# 3dglove_p1.net
KiCad netlist of a schematic drawn in EAGLE
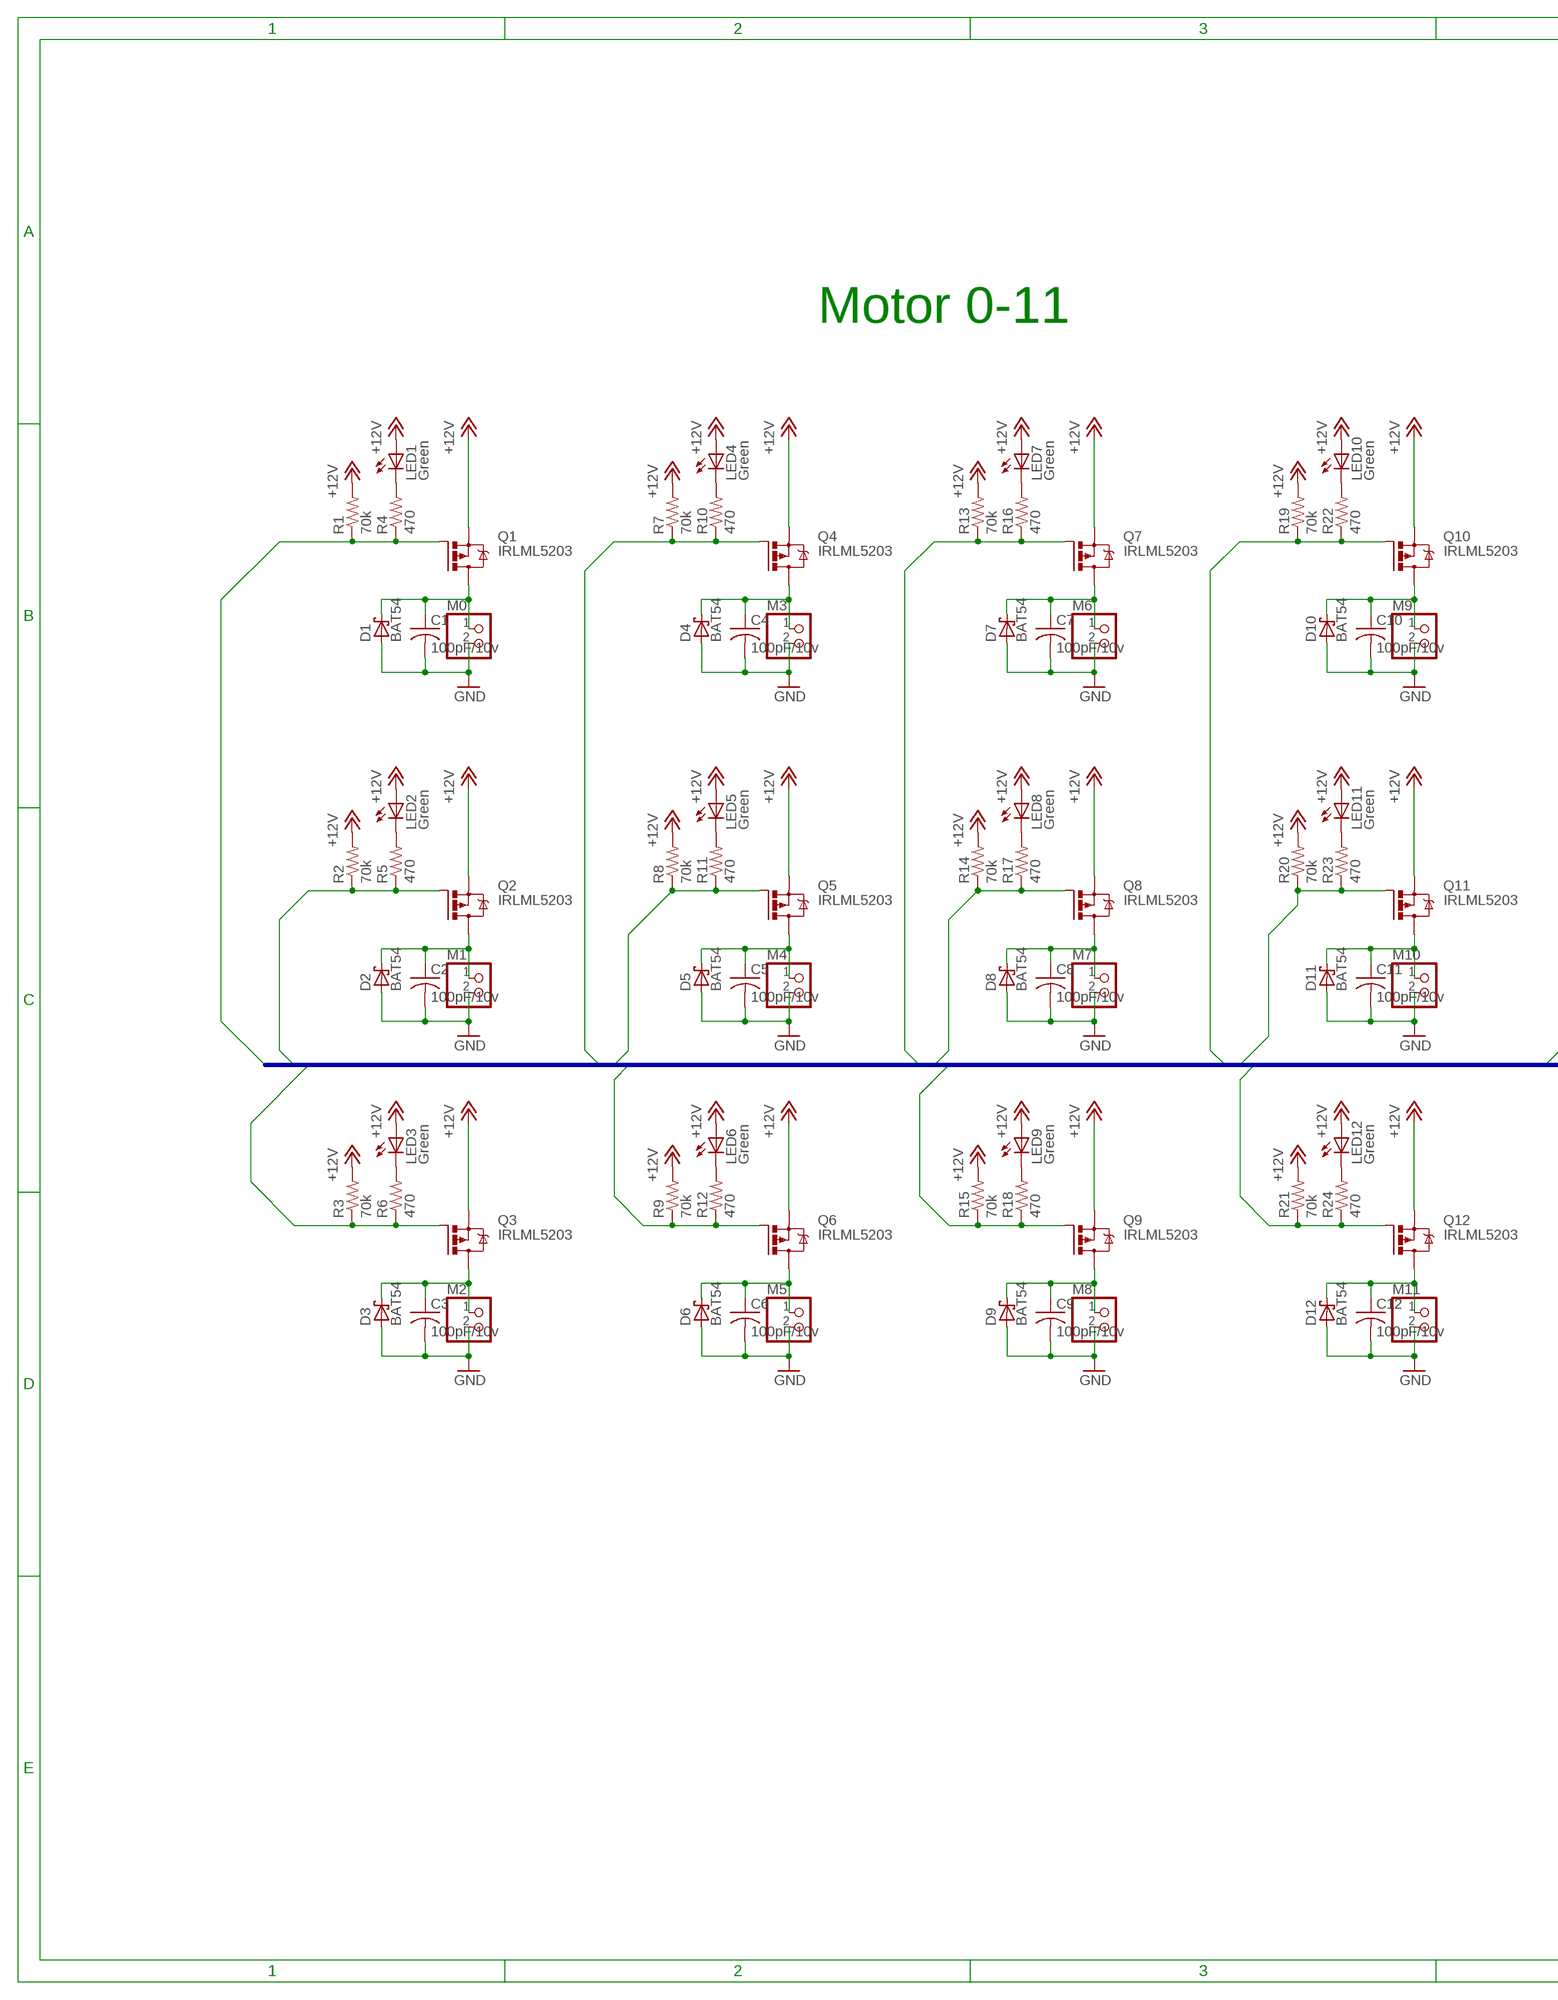
[diagram p0: schematic, sheet 1, part 1 of 2]
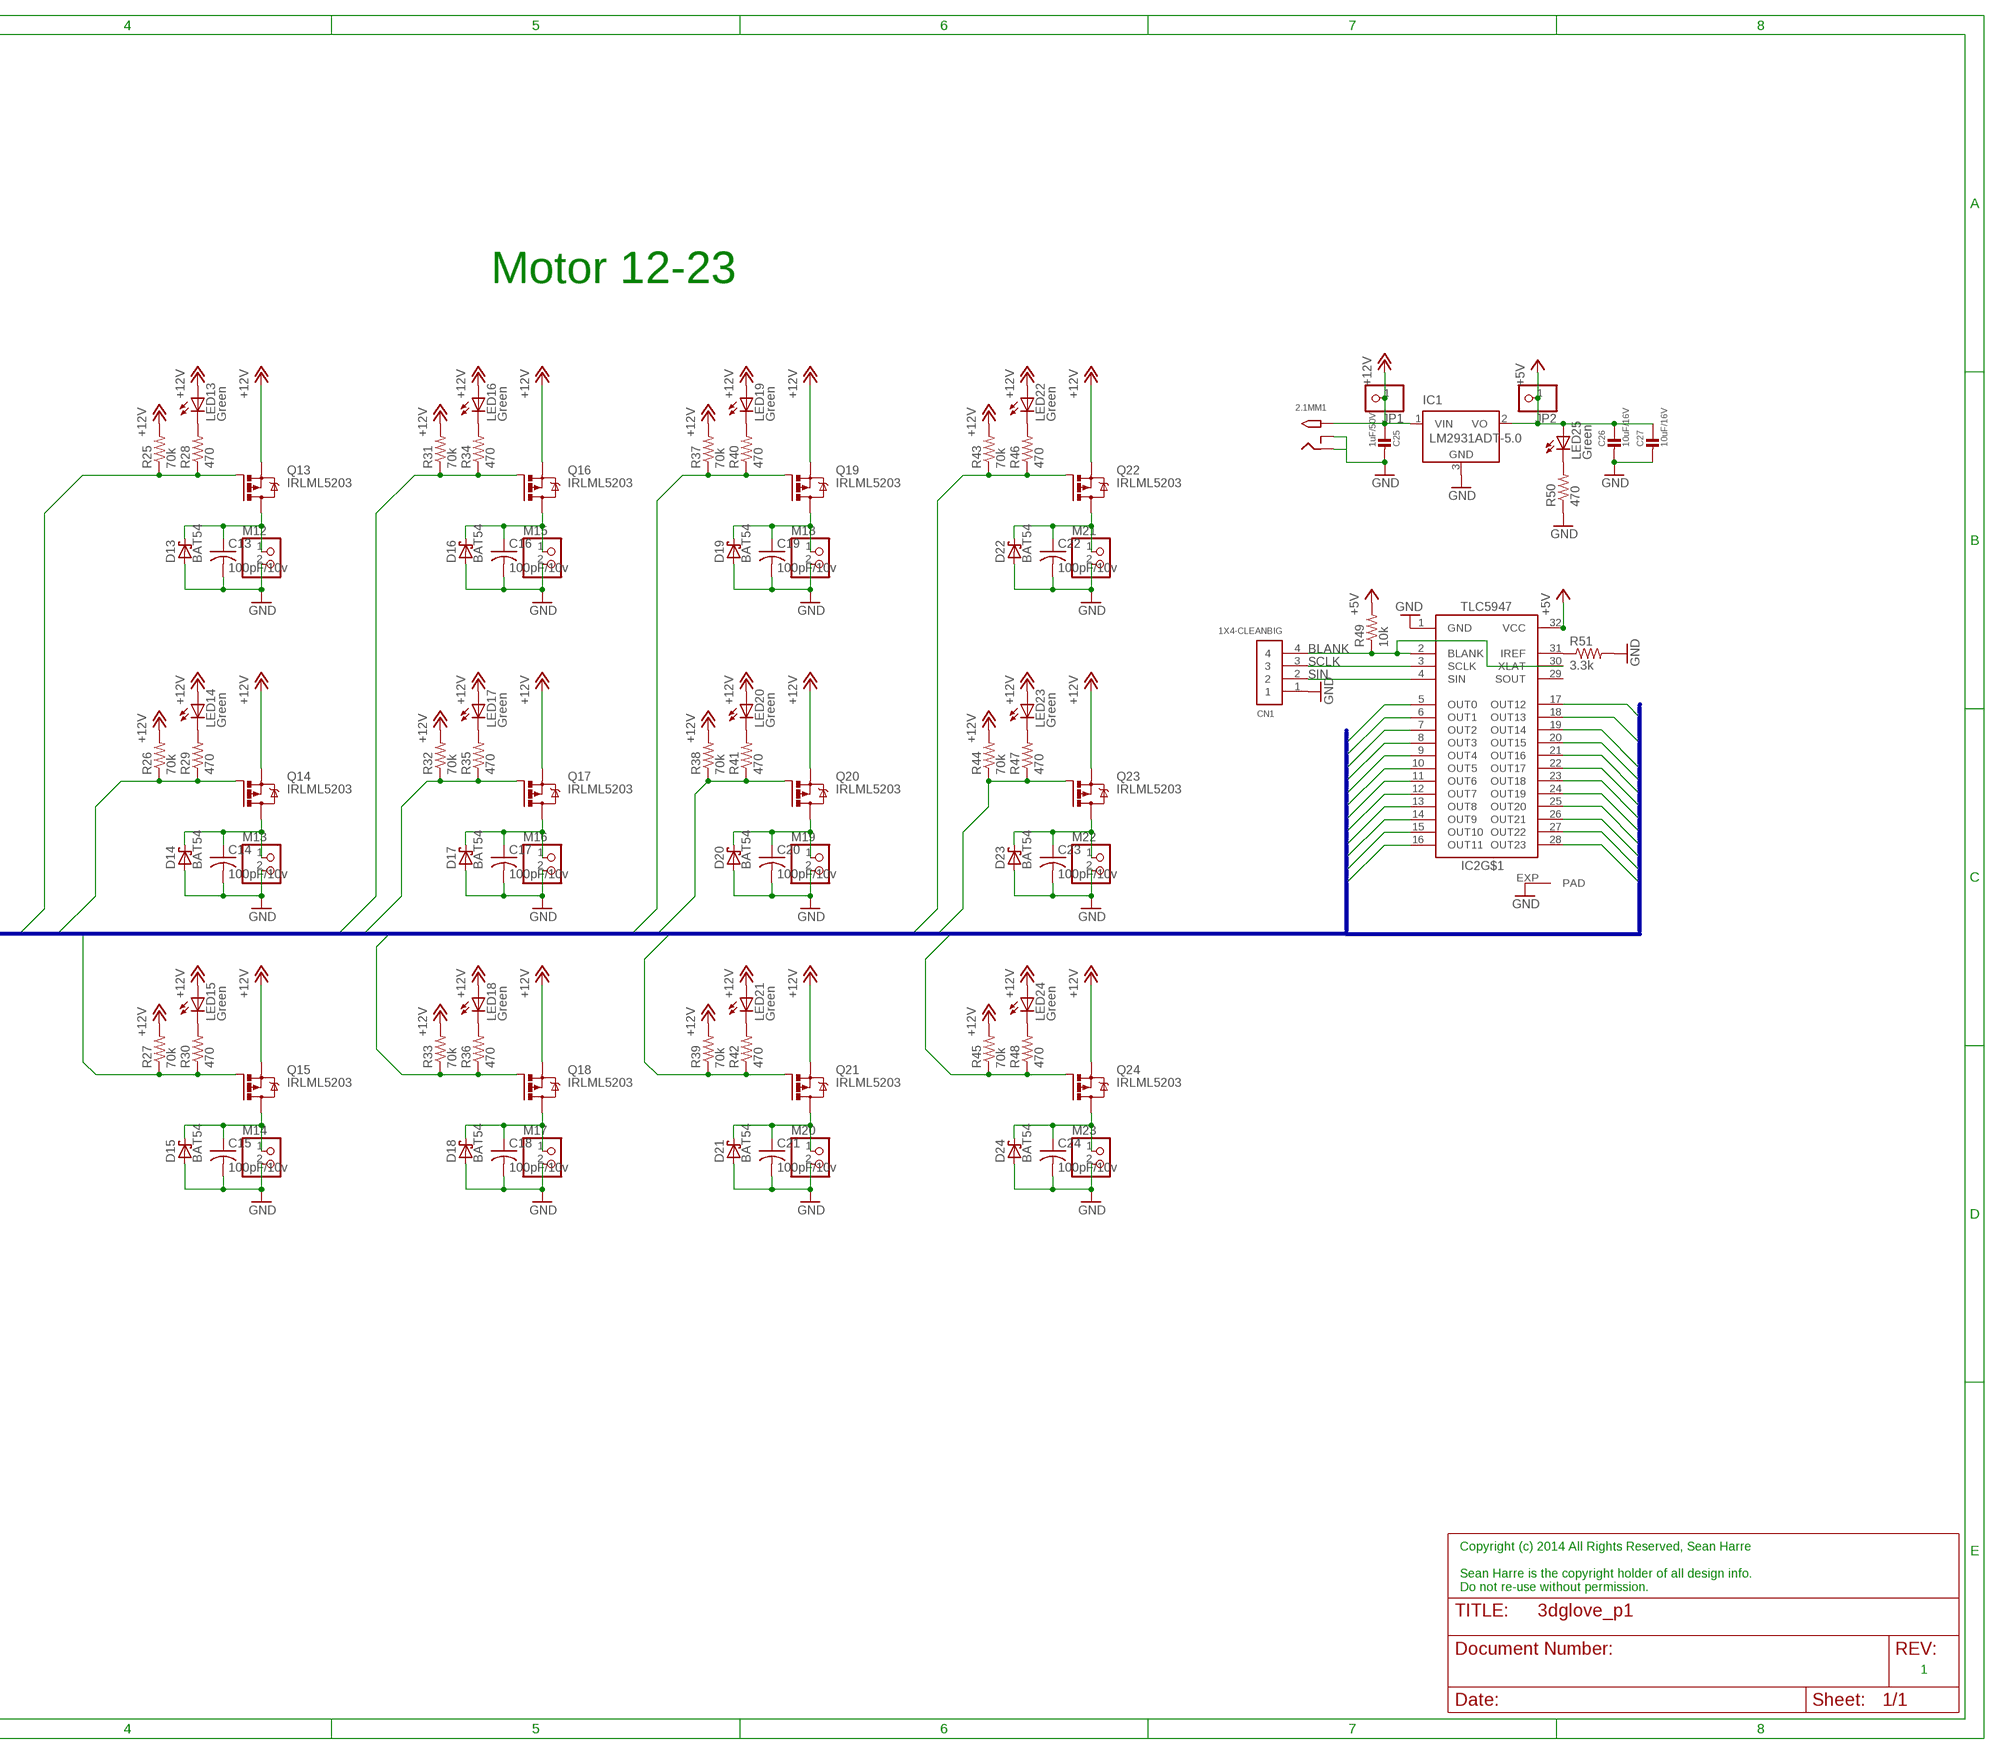
[diagram p1: schematic, sheet 1, part 2 of 2]

(export (version "E")
  (design (tool "Eeschema 10.0.6"))
  (components
    (comp (ref "2.1MM1")
      (value "2.1MMJACKTHM")
      (footprint "eagle-import:PJ-102A")
      (fields (field (name "MF") "FARNELL") (field (name "MPN") "DC10A"))
      (libsource (lib "eagle-import") (part "2.1MMJACKTHM"))
    )
    (comp (ref "C1")
      (value "100pF/10v")
      (footprint "eagle-import:C0402")
      (fields (field (name "MPN") "MCMT15N101F100CT"))
      (libsource (lib "eagle-import") (part "C-USC0402"))
    )
    (comp (ref "C2")
      (value "100pF/10v")
      (footprint "eagle-import:C0402")
      (fields (field (name "MPN") "MCMT15N101F100CT"))
      (libsource (lib "eagle-import") (part "C-USC0402"))
    )
    (comp (ref "C3")
      (value "100pF/10v")
      (footprint "eagle-import:C0402")
      (fields (field (name "MPN") "MCMT15N101F100CT"))
      (libsource (lib "eagle-import") (part "C-USC0402"))
    )
    (comp (ref "C4")
      (value "100pF/10v")
      (footprint "eagle-import:C0402")
      (fields (field (name "MPN") "MCMT15N101F100CT"))
      (libsource (lib "eagle-import") (part "C-USC0402"))
    )
    (comp (ref "C5")
      (value "100pF/10v")
      (footprint "eagle-import:C0402")
      (fields (field (name "MPN") "MCMT15N101F100CT"))
      (libsource (lib "eagle-import") (part "C-USC0402"))
    )
    (comp (ref "C6")
      (value "100pF/10v")
      (footprint "eagle-import:C0402")
      (fields (field (name "MPN") "MCMT15N101F100CT"))
      (libsource (lib "eagle-import") (part "C-USC0402"))
    )
    (comp (ref "C7")
      (value "100pF/10v")
      (footprint "eagle-import:C0402")
      (fields (field (name "MPN") "MCMT15N101F100CT"))
      (libsource (lib "eagle-import") (part "C-USC0402"))
    )
    (comp (ref "C8")
      (value "100pF/10v")
      (footprint "eagle-import:C0402")
      (fields (field (name "MPN") "MCMT15N101F100CT"))
      (libsource (lib "eagle-import") (part "C-USC0402"))
    )
    (comp (ref "C9")
      (value "100pF/10v")
      (footprint "eagle-import:C0402")
      (fields (field (name "MPN") "MCMT15N101F100CT"))
      (libsource (lib "eagle-import") (part "C-USC0402"))
    )
    (comp (ref "C10")
      (value "100pF/10v")
      (footprint "eagle-import:C0402")
      (fields (field (name "MPN") "MCMT15N101F100CT"))
      (libsource (lib "eagle-import") (part "C-USC0402"))
    )
    (comp (ref "C11")
      (value "100pF/10v")
      (footprint "eagle-import:C0402")
      (fields (field (name "MPN") "MCMT15N101F100CT"))
      (libsource (lib "eagle-import") (part "C-USC0402"))
    )
    (comp (ref "C12")
      (value "100pF/10v")
      (footprint "eagle-import:C0402")
      (fields (field (name "MPN") "MCMT15N101F100CT"))
      (libsource (lib "eagle-import") (part "C-USC0402"))
    )
    (comp (ref "C13")
      (value "100pF/10v")
      (footprint "eagle-import:C0402")
      (fields (field (name "MPN") "MCMT15N101F100CT"))
      (libsource (lib "eagle-import") (part "C-USC0402"))
    )
    (comp (ref "C14")
      (value "100pF/10v")
      (footprint "eagle-import:C0402")
      (fields (field (name "MPN") "MCMT15N101F100CT"))
      (libsource (lib "eagle-import") (part "C-USC0402"))
    )
    (comp (ref "C15")
      (value "100pF/10v")
      (footprint "eagle-import:C0402")
      (fields (field (name "MPN") "MCMT15N101F100CT"))
      (libsource (lib "eagle-import") (part "C-USC0402"))
    )
    (comp (ref "C16")
      (value "100pF/10v")
      (footprint "eagle-import:C0402")
      (fields (field (name "MPN") "MCMT15N101F100CT"))
      (libsource (lib "eagle-import") (part "C-USC0402"))
    )
    (comp (ref "C17")
      (value "100pF/10v")
      (footprint "eagle-import:C0402")
      (fields (field (name "MPN") "MCMT15N101F100CT"))
      (libsource (lib "eagle-import") (part "C-USC0402"))
    )
    (comp (ref "C18")
      (value "100pF/10v")
      (footprint "eagle-import:C0402")
      (fields (field (name "MPN") "MCMT15N101F100CT"))
      (libsource (lib "eagle-import") (part "C-USC0402"))
    )
    (comp (ref "C19")
      (value "100pF/10v")
      (footprint "eagle-import:C0402")
      (fields (field (name "MPN") "MCMT15N101F100CT"))
      (libsource (lib "eagle-import") (part "C-USC0402"))
    )
    (comp (ref "C20")
      (value "100pF/10v")
      (footprint "eagle-import:C0402")
      (fields (field (name "MPN") "MCMT15N101F100CT"))
      (libsource (lib "eagle-import") (part "C-USC0402"))
    )
    (comp (ref "C21")
      (value "100pF/10v")
      (footprint "eagle-import:C0402")
      (fields (field (name "MPN") "MCMT15N101F100CT"))
      (libsource (lib "eagle-import") (part "C-USC0402"))
    )
    (comp (ref "C22")
      (value "100pF/10v")
      (footprint "eagle-import:C0402")
      (fields (field (name "MPN") "MCMT15N101F100CT"))
      (libsource (lib "eagle-import") (part "C-USC0402"))
    )
    (comp (ref "C23")
      (value "100pF/10v")
      (footprint "eagle-import:C0402")
      (fields (field (name "MPN") "MCMT15N101F100CT"))
      (libsource (lib "eagle-import") (part "C-USC0402"))
    )
    (comp (ref "C24")
      (value "100pF/10v")
      (footprint "eagle-import:C0402")
      (fields (field (name "MPN") "MCMT15N101F100CT"))
      (libsource (lib "eagle-import") (part "C-USC0402"))
    )
    (comp (ref "C25")
      (value "1uF/50V")
      (footprint "eagle-import:0805")
      (fields (field (name "MPN") "C2012X7R1H105K125AB"))
      (libsource (lib "eagle-import") (part "CAP_CERAMIC0805"))
    )
    (comp (ref "C26")
      (value "10uF/16V")
      (footprint "eagle-import:0805")
      (fields (field (name "MPN") "C2012X5R1C106K085AC"))
      (libsource (lib "eagle-import") (part "CAP_CERAMIC0805"))
    )
    (comp (ref "C27")
      (value "10uF/16V")
      (footprint "eagle-import:0805")
      (fields (field (name "MPN") "C2012X5R1C106K085AC"))
      (libsource (lib "eagle-import") (part "CAP_CERAMIC0805"))
    )
    (comp (ref "CN1")
      (value "1X4-CLEANBIG")
      (footprint "eagle-import:1X04-CLEANBIG")
      (libsource (lib "eagle-import") (part "1X4-CLEANBIG"))
    )
    (comp (ref "D1")
      (value "BAT54")
      (footprint "eagle-import:SOT23")
      (fields (field (name "MF") "ON SEMICONDUCTOR") (field (name "MPN") "BAT54LT1G"))
      (libsource (lib "eagle-import") (part "BAT54"))
    )
    (comp (ref "D2")
      (value "BAT54")
      (footprint "eagle-import:SOT23")
      (fields (field (name "MF") "ON SEMICONDUCTOR") (field (name "MPN") "BAT54LT1G"))
      (libsource (lib "eagle-import") (part "BAT54"))
    )
    (comp (ref "D3")
      (value "BAT54")
      (footprint "eagle-import:SOT23")
      (fields (field (name "MF") "ON SEMICONDUCTOR") (field (name "MPN") "BAT54LT1G"))
      (libsource (lib "eagle-import") (part "BAT54"))
    )
    (comp (ref "D4")
      (value "BAT54")
      (footprint "eagle-import:SOT23")
      (fields (field (name "MF") "ON SEMICONDUCTOR") (field (name "MPN") "BAT54LT1G"))
      (libsource (lib "eagle-import") (part "BAT54"))
    )
    (comp (ref "D5")
      (value "BAT54")
      (footprint "eagle-import:SOT23")
      (fields (field (name "MF") "ON SEMICONDUCTOR") (field (name "MPN") "BAT54LT1G"))
      (libsource (lib "eagle-import") (part "BAT54"))
    )
    (comp (ref "D6")
      (value "BAT54")
      (footprint "eagle-import:SOT23")
      (fields (field (name "MF") "ON SEMICONDUCTOR") (field (name "MPN") "BAT54LT1G"))
      (libsource (lib "eagle-import") (part "BAT54"))
    )
    (comp (ref "D7")
      (value "BAT54")
      (footprint "eagle-import:SOT23")
      (fields (field (name "MF") "ON SEMICONDUCTOR") (field (name "MPN") "BAT54LT1G"))
      (libsource (lib "eagle-import") (part "BAT54"))
    )
    (comp (ref "D8")
      (value "BAT54")
      (footprint "eagle-import:SOT23")
      (fields (field (name "MF") "ON SEMICONDUCTOR") (field (name "MPN") "BAT54LT1G"))
      (libsource (lib "eagle-import") (part "BAT54"))
    )
    (comp (ref "D9")
      (value "BAT54")
      (footprint "eagle-import:SOT23")
      (fields (field (name "MF") "ON SEMICONDUCTOR") (field (name "MPN") "BAT54LT1G"))
      (libsource (lib "eagle-import") (part "BAT54"))
    )
    (comp (ref "D10")
      (value "BAT54")
      (footprint "eagle-import:SOT23")
      (fields (field (name "MF") "ON SEMICONDUCTOR") (field (name "MPN") "BAT54LT1G"))
      (libsource (lib "eagle-import") (part "BAT54"))
    )
    (comp (ref "D11")
      (value "BAT54")
      (footprint "eagle-import:SOT23")
      (fields (field (name "MF") "ON SEMICONDUCTOR") (field (name "MPN") "BAT54LT1G"))
      (libsource (lib "eagle-import") (part "BAT54"))
    )
    (comp (ref "D12")
      (value "BAT54")
      (footprint "eagle-import:SOT23")
      (fields (field (name "MF") "ON SEMICONDUCTOR") (field (name "MPN") "BAT54LT1G"))
      (libsource (lib "eagle-import") (part "BAT54"))
    )
    (comp (ref "D13")
      (value "BAT54")
      (footprint "eagle-import:SOT23")
      (fields (field (name "MF") "ON SEMICONDUCTOR") (field (name "MPN") "BAT54LT1G"))
      (libsource (lib "eagle-import") (part "BAT54"))
    )
    (comp (ref "D14")
      (value "BAT54")
      (footprint "eagle-import:SOT23")
      (fields (field (name "MF") "ON SEMICONDUCTOR") (field (name "MPN") "BAT54LT1G"))
      (libsource (lib "eagle-import") (part "BAT54"))
    )
    (comp (ref "D15")
      (value "BAT54")
      (footprint "eagle-import:SOT23")
      (fields (field (name "MF") "ON SEMICONDUCTOR") (field (name "MPN") "BAT54LT1G"))
      (libsource (lib "eagle-import") (part "BAT54"))
    )
    (comp (ref "D16")
      (value "BAT54")
      (footprint "eagle-import:SOT23")
      (fields (field (name "MF") "ON SEMICONDUCTOR") (field (name "MPN") "BAT54LT1G"))
      (libsource (lib "eagle-import") (part "BAT54"))
    )
    (comp (ref "D17")
      (value "BAT54")
      (footprint "eagle-import:SOT23")
      (fields (field (name "MF") "ON SEMICONDUCTOR") (field (name "MPN") "BAT54LT1G"))
      (libsource (lib "eagle-import") (part "BAT54"))
    )
    (comp (ref "D18")
      (value "BAT54")
      (footprint "eagle-import:SOT23")
      (fields (field (name "MF") "ON SEMICONDUCTOR") (field (name "MPN") "BAT54LT1G"))
      (libsource (lib "eagle-import") (part "BAT54"))
    )
    (comp (ref "D19")
      (value "BAT54")
      (footprint "eagle-import:SOT23")
      (fields (field (name "MF") "ON SEMICONDUCTOR") (field (name "MPN") "BAT54LT1G"))
      (libsource (lib "eagle-import") (part "BAT54"))
    )
    (comp (ref "D20")
      (value "BAT54")
      (footprint "eagle-import:SOT23")
      (fields (field (name "MF") "ON SEMICONDUCTOR") (field (name "MPN") "BAT54LT1G"))
      (libsource (lib "eagle-import") (part "BAT54"))
    )
    (comp (ref "D21")
      (value "BAT54")
      (footprint "eagle-import:SOT23")
      (fields (field (name "MF") "ON SEMICONDUCTOR") (field (name "MPN") "BAT54LT1G"))
      (libsource (lib "eagle-import") (part "BAT54"))
    )
    (comp (ref "D22")
      (value "BAT54")
      (footprint "eagle-import:SOT23")
      (fields (field (name "MF") "ON SEMICONDUCTOR") (field (name "MPN") "BAT54LT1G"))
      (libsource (lib "eagle-import") (part "BAT54"))
    )
    (comp (ref "D23")
      (value "BAT54")
      (footprint "eagle-import:SOT23")
      (fields (field (name "MF") "ON SEMICONDUCTOR") (field (name "MPN") "BAT54LT1G"))
      (libsource (lib "eagle-import") (part "BAT54"))
    )
    (comp (ref "D24")
      (value "BAT54")
      (footprint "eagle-import:SOT23")
      (fields (field (name "MF") "ON SEMICONDUCTOR") (field (name "MPN") "BAT54LT1G"))
      (libsource (lib "eagle-import") (part "BAT54"))
    )
    (comp (ref "IC1")
      (value "LM2931ADT-5.0")
      (footprint "eagle-import:TO252")
      (fields (field (name "MPN") "LM2936DT-3.3."))
      (libsource (lib "eagle-import") (part "LM2936?DT-3.3"))
    )
    (comp (ref "IC2")
      (value "TLC5947-DAP")
      (footprint "eagle-import:HTSSOP32DAP")
      (fields (field (name "MPN") "TLC5947DAP") (field (name "OC_NEWARK") "03P5011"))
      (libsource (lib "eagle-import") (part "TLC5947-DAP"))
    )
    (comp (ref "JP1")
      (value "PINHD-1X1CB")
      (footprint "eagle-import:1X01-CLEANBIG")
      (libsource (lib "eagle-import") (part "PINHD-1X1CB"))
    )
    (comp (ref "JP2")
      (value "PINHD-1X1CB")
      (footprint "eagle-import:1X01-CLEANBIG")
      (libsource (lib "eagle-import") (part "PINHD-1X1CB"))
    )
    (comp (ref "LED1")
      (value "Green")
      (footprint "eagle-import:CHIP-LED0805")
      (libsource (lib "eagle-import") (part "LEDCHIP-LED0805"))
    )
    (comp (ref "LED2")
      (value "Green")
      (footprint "eagle-import:CHIP-LED0805")
      (libsource (lib "eagle-import") (part "LEDCHIP-LED0805"))
    )
    (comp (ref "LED3")
      (value "Green")
      (footprint "eagle-import:CHIP-LED0805")
      (libsource (lib "eagle-import") (part "LEDCHIP-LED0805"))
    )
    (comp (ref "LED4")
      (value "Green")
      (footprint "eagle-import:CHIP-LED0805")
      (libsource (lib "eagle-import") (part "LEDCHIP-LED0805"))
    )
    (comp (ref "LED5")
      (value "Green")
      (footprint "eagle-import:CHIP-LED0805")
      (libsource (lib "eagle-import") (part "LEDCHIP-LED0805"))
    )
    (comp (ref "LED6")
      (value "Green")
      (footprint "eagle-import:CHIP-LED0805")
      (libsource (lib "eagle-import") (part "LEDCHIP-LED0805"))
    )
    (comp (ref "LED7")
      (value "Green")
      (footprint "eagle-import:CHIP-LED0805")
      (libsource (lib "eagle-import") (part "LEDCHIP-LED0805"))
    )
    (comp (ref "LED8")
      (value "Green")
      (footprint "eagle-import:CHIP-LED0805")
      (libsource (lib "eagle-import") (part "LEDCHIP-LED0805"))
    )
    (comp (ref "LED9")
      (value "Green")
      (footprint "eagle-import:CHIP-LED0805")
      (libsource (lib "eagle-import") (part "LEDCHIP-LED0805"))
    )
    (comp (ref "LED10")
      (value "Green")
      (footprint "eagle-import:CHIP-LED0805")
      (libsource (lib "eagle-import") (part "LEDCHIP-LED0805"))
    )
    (comp (ref "LED11")
      (value "Green")
      (footprint "eagle-import:CHIP-LED0805")
      (libsource (lib "eagle-import") (part "LEDCHIP-LED0805"))
    )
    (comp (ref "LED12")
      (value "Green")
      (footprint "eagle-import:CHIP-LED0805")
      (libsource (lib "eagle-import") (part "LEDCHIP-LED0805"))
    )
    (comp (ref "LED13")
      (value "Green")
      (footprint "eagle-import:CHIP-LED0805")
      (libsource (lib "eagle-import") (part "LEDCHIP-LED0805"))
    )
    (comp (ref "LED14")
      (value "Green")
      (footprint "eagle-import:CHIP-LED0805")
      (libsource (lib "eagle-import") (part "LEDCHIP-LED0805"))
    )
    (comp (ref "LED15")
      (value "Green")
      (footprint "eagle-import:CHIP-LED0805")
      (libsource (lib "eagle-import") (part "LEDCHIP-LED0805"))
    )
    (comp (ref "LED16")
      (value "Green")
      (footprint "eagle-import:CHIP-LED0805")
      (libsource (lib "eagle-import") (part "LEDCHIP-LED0805"))
    )
    (comp (ref "LED17")
      (value "Green")
      (footprint "eagle-import:CHIP-LED0805")
      (libsource (lib "eagle-import") (part "LEDCHIP-LED0805"))
    )
    (comp (ref "LED18")
      (value "Green")
      (footprint "eagle-import:CHIP-LED0805")
      (libsource (lib "eagle-import") (part "LEDCHIP-LED0805"))
    )
    (comp (ref "LED19")
      (value "Green")
      (footprint "eagle-import:CHIP-LED0805")
      (libsource (lib "eagle-import") (part "LEDCHIP-LED0805"))
    )
    (comp (ref "LED20")
      (value "Green")
      (footprint "eagle-import:CHIP-LED0805")
      (libsource (lib "eagle-import") (part "LEDCHIP-LED0805"))
    )
    (comp (ref "LED21")
      (value "Green")
      (footprint "eagle-import:CHIP-LED0805")
      (libsource (lib "eagle-import") (part "LEDCHIP-LED0805"))
    )
    (comp (ref "LED22")
      (value "Green")
      (footprint "eagle-import:CHIP-LED0805")
      (libsource (lib "eagle-import") (part "LEDCHIP-LED0805"))
    )
    (comp (ref "LED23")
      (value "Green")
      (footprint "eagle-import:CHIP-LED0805")
      (libsource (lib "eagle-import") (part "LEDCHIP-LED0805"))
    )
    (comp (ref "LED24")
      (value "Green")
      (footprint "eagle-import:CHIP-LED0805")
      (libsource (lib "eagle-import") (part "LEDCHIP-LED0805"))
    )
    (comp (ref "LED25")
      (value "Green")
      (footprint "eagle-import:CHIP-LED0805")
      (libsource (lib "eagle-import") (part "LEDCHIP-LED0805"))
    )
    (comp (ref "M0")
      (value "PINHD-1X2")
      (footprint "eagle-import:1X02")
      (libsource (lib "eagle-import") (part "PINHD-1X2"))
    )
    (comp (ref "M1")
      (value "PINHD-1X2")
      (footprint "eagle-import:1X02")
      (libsource (lib "eagle-import") (part "PINHD-1X2"))
    )
    (comp (ref "M2")
      (value "PINHD-1X2")
      (footprint "eagle-import:1X02")
      (libsource (lib "eagle-import") (part "PINHD-1X2"))
    )
    (comp (ref "M3")
      (value "PINHD-1X2")
      (footprint "eagle-import:1X02")
      (libsource (lib "eagle-import") (part "PINHD-1X2"))
    )
    (comp (ref "M4")
      (value "PINHD-1X2")
      (footprint "eagle-import:1X02")
      (libsource (lib "eagle-import") (part "PINHD-1X2"))
    )
    (comp (ref "M5")
      (value "PINHD-1X2")
      (footprint "eagle-import:1X02")
      (libsource (lib "eagle-import") (part "PINHD-1X2"))
    )
    (comp (ref "M6")
      (value "PINHD-1X2")
      (footprint "eagle-import:1X02")
      (libsource (lib "eagle-import") (part "PINHD-1X2"))
    )
    (comp (ref "M7")
      (value "PINHD-1X2")
      (footprint "eagle-import:1X02")
      (libsource (lib "eagle-import") (part "PINHD-1X2"))
    )
    (comp (ref "M8")
      (value "PINHD-1X2")
      (footprint "eagle-import:1X02")
      (libsource (lib "eagle-import") (part "PINHD-1X2"))
    )
    (comp (ref "M9")
      (value "PINHD-1X2")
      (footprint "eagle-import:1X02")
      (libsource (lib "eagle-import") (part "PINHD-1X2"))
    )
    (comp (ref "M10")
      (value "PINHD-1X2")
      (footprint "eagle-import:1X02")
      (libsource (lib "eagle-import") (part "PINHD-1X2"))
    )
    (comp (ref "M11")
      (value "PINHD-1X2")
      (footprint "eagle-import:1X02")
      (libsource (lib "eagle-import") (part "PINHD-1X2"))
    )
    (comp (ref "M12")
      (value "PINHD-1X2")
      (footprint "eagle-import:1X02")
      (libsource (lib "eagle-import") (part "PINHD-1X2"))
    )
    (comp (ref "M13")
      (value "PINHD-1X2")
      (footprint "eagle-import:1X02")
      (libsource (lib "eagle-import") (part "PINHD-1X2"))
    )
    (comp (ref "M14")
      (value "PINHD-1X2")
      (footprint "eagle-import:1X02")
      (libsource (lib "eagle-import") (part "PINHD-1X2"))
    )
    (comp (ref "M15")
      (value "PINHD-1X2")
      (footprint "eagle-import:1X02")
      (libsource (lib "eagle-import") (part "PINHD-1X2"))
    )
    (comp (ref "M16")
      (value "PINHD-1X2")
      (footprint "eagle-import:1X02")
      (libsource (lib "eagle-import") (part "PINHD-1X2"))
    )
    (comp (ref "M17")
      (value "PINHD-1X2")
      (footprint "eagle-import:1X02")
      (libsource (lib "eagle-import") (part "PINHD-1X2"))
    )
    (comp (ref "M18")
      (value "PINHD-1X2")
      (footprint "eagle-import:1X02")
      (libsource (lib "eagle-import") (part "PINHD-1X2"))
    )
    (comp (ref "M19")
      (value "PINHD-1X2")
      (footprint "eagle-import:1X02")
      (libsource (lib "eagle-import") (part "PINHD-1X2"))
    )
    (comp (ref "M20")
      (value "PINHD-1X2")
      (footprint "eagle-import:1X02")
      (libsource (lib "eagle-import") (part "PINHD-1X2"))
    )
    (comp (ref "M21")
      (value "PINHD-1X2")
      (footprint "eagle-import:1X02")
      (libsource (lib "eagle-import") (part "PINHD-1X2"))
    )
    (comp (ref "M22")
      (value "PINHD-1X2")
      (footprint "eagle-import:1X02")
      (libsource (lib "eagle-import") (part "PINHD-1X2"))
    )
    (comp (ref "M23")
      (value "PINHD-1X2")
      (footprint "eagle-import:1X02")
      (libsource (lib "eagle-import") (part "PINHD-1X2"))
    )
    (comp (ref "Q1")
      (value "IRLML5203")
      (footprint "eagle-import:MICRO3")
      (fields (field (name "MPN") "IRLML5203GTRPBF"))
      (libsource (lib "eagle-import") (part "IRLML5203"))
    )
    (comp (ref "Q2")
      (value "IRLML5203")
      (footprint "eagle-import:MICRO3")
      (fields (field (name "MPN") "IRLML5203GTRPBF"))
      (libsource (lib "eagle-import") (part "IRLML5203"))
    )
    (comp (ref "Q3")
      (value "IRLML5203")
      (footprint "eagle-import:MICRO3")
      (fields (field (name "MPN") "IRLML5203GTRPBF"))
      (libsource (lib "eagle-import") (part "IRLML5203"))
    )
    (comp (ref "Q4")
      (value "IRLML5203")
      (footprint "eagle-import:MICRO3")
      (fields (field (name "MPN") "IRLML5203GTRPBF"))
      (libsource (lib "eagle-import") (part "IRLML5203"))
    )
    (comp (ref "Q5")
      (value "IRLML5203")
      (footprint "eagle-import:MICRO3")
      (fields (field (name "MPN") "IRLML5203GTRPBF"))
      (libsource (lib "eagle-import") (part "IRLML5203"))
    )
    (comp (ref "Q6")
      (value "IRLML5203")
      (footprint "eagle-import:MICRO3")
      (fields (field (name "MPN") "IRLML5203GTRPBF"))
      (libsource (lib "eagle-import") (part "IRLML5203"))
    )
    (comp (ref "Q7")
      (value "IRLML5203")
      (footprint "eagle-import:MICRO3")
      (fields (field (name "MPN") "IRLML5203GTRPBF"))
      (libsource (lib "eagle-import") (part "IRLML5203"))
    )
    (comp (ref "Q8")
      (value "IRLML5203")
      (footprint "eagle-import:MICRO3")
      (fields (field (name "MPN") "IRLML5203GTRPBF"))
      (libsource (lib "eagle-import") (part "IRLML5203"))
    )
    (comp (ref "Q9")
      (value "IRLML5203")
      (footprint "eagle-import:MICRO3")
      (fields (field (name "MPN") "IRLML5203GTRPBF"))
      (libsource (lib "eagle-import") (part "IRLML5203"))
    )
    (comp (ref "Q10")
      (value "IRLML5203")
      (footprint "eagle-import:MICRO3")
      (fields (field (name "MPN") "IRLML5203GTRPBF"))
      (libsource (lib "eagle-import") (part "IRLML5203"))
    )
    (comp (ref "Q11")
      (value "IRLML5203")
      (footprint "eagle-import:MICRO3")
      (fields (field (name "MPN") "IRLML5203GTRPBF"))
      (libsource (lib "eagle-import") (part "IRLML5203"))
    )
    (comp (ref "Q12")
      (value "IRLML5203")
      (footprint "eagle-import:MICRO3")
      (fields (field (name "MPN") "IRLML5203GTRPBF"))
      (libsource (lib "eagle-import") (part "IRLML5203"))
    )
    (comp (ref "Q13")
      (value "IRLML5203")
      (footprint "eagle-import:MICRO3")
      (fields (field (name "MPN") "IRLML5203GTRPBF"))
      (libsource (lib "eagle-import") (part "IRLML5203"))
    )
    (comp (ref "Q14")
      (value "IRLML5203")
      (footprint "eagle-import:MICRO3")
      (fields (field (name "MPN") "IRLML5203GTRPBF"))
      (libsource (lib "eagle-import") (part "IRLML5203"))
    )
    (comp (ref "Q15")
      (value "IRLML5203")
      (footprint "eagle-import:MICRO3")
      (fields (field (name "MPN") "IRLML5203GTRPBF"))
      (libsource (lib "eagle-import") (part "IRLML5203"))
    )
    (comp (ref "Q16")
      (value "IRLML5203")
      (footprint "eagle-import:MICRO3")
      (fields (field (name "MPN") "IRLML5203GTRPBF"))
      (libsource (lib "eagle-import") (part "IRLML5203"))
    )
    (comp (ref "Q17")
      (value "IRLML5203")
      (footprint "eagle-import:MICRO3")
      (fields (field (name "MPN") "IRLML5203GTRPBF"))
      (libsource (lib "eagle-import") (part "IRLML5203"))
    )
    (comp (ref "Q18")
      (value "IRLML5203")
      (footprint "eagle-import:MICRO3")
      (fields (field (name "MPN") "IRLML5203GTRPBF"))
      (libsource (lib "eagle-import") (part "IRLML5203"))
    )
    (comp (ref "Q19")
      (value "IRLML5203")
      (footprint "eagle-import:MICRO3")
      (fields (field (name "MPN") "IRLML5203GTRPBF"))
      (libsource (lib "eagle-import") (part "IRLML5203"))
    )
    (comp (ref "Q20")
      (value "IRLML5203")
      (footprint "eagle-import:MICRO3")
      (fields (field (name "MPN") "IRLML5203GTRPBF"))
      (libsource (lib "eagle-import") (part "IRLML5203"))
    )
    (comp (ref "Q21")
      (value "IRLML5203")
      (footprint "eagle-import:MICRO3")
      (fields (field (name "MPN") "IRLML5203GTRPBF"))
      (libsource (lib "eagle-import") (part "IRLML5203"))
    )
    (comp (ref "Q22")
      (value "IRLML5203")
      (footprint "eagle-import:MICRO3")
      (fields (field (name "MPN") "IRLML5203GTRPBF"))
      (libsource (lib "eagle-import") (part "IRLML5203"))
    )
    (comp (ref "Q23")
      (value "IRLML5203")
      (footprint "eagle-import:MICRO3")
      (fields (field (name "MPN") "IRLML5203GTRPBF"))
      (libsource (lib "eagle-import") (part "IRLML5203"))
    )
    (comp (ref "Q24")
      (value "IRLML5203")
      (footprint "eagle-import:MICRO3")
      (fields (field (name "MPN") "IRLML5203GTRPBF"))
      (libsource (lib "eagle-import") (part "IRLML5203"))
    )
    (comp (ref "R1")
      (value "70k")
      (footprint "eagle-import:R0402")
      (fields (field (name "MPN") "ERJ-2GEJ683X"))
      (libsource (lib "eagle-import") (part "R-US_R0402"))
    )
    (comp (ref "R2")
      (value "70k")
      (footprint "eagle-import:R0402")
      (fields (field (name "MPN") "ERJ-2GEJ683X"))
      (libsource (lib "eagle-import") (part "R-US_R0402"))
    )
    (comp (ref "R3")
      (value "70k")
      (footprint "eagle-import:R0402")
      (fields (field (name "MPN") "ERJ-2GEJ683X"))
      (libsource (lib "eagle-import") (part "R-US_R0402"))
    )
    (comp (ref "R4")
      (value "470")
      (footprint "eagle-import:R1206")
      (fields (field (name "MPN") "MCHP06W2F4700T5E"))
      (libsource (lib "eagle-import") (part "R-US_R1206"))
    )
    (comp (ref "R5")
      (value "470")
      (footprint "eagle-import:R1206")
      (fields (field (name "MPN") "MCHP06W2F4700T5E"))
      (libsource (lib "eagle-import") (part "R-US_R1206"))
    )
    (comp (ref "R6")
      (value "470")
      (footprint "eagle-import:R1206")
      (fields (field (name "MPN") "MCHP06W2F4700T5E"))
      (libsource (lib "eagle-import") (part "R-US_R1206"))
    )
    (comp (ref "R7")
      (value "70k")
      (footprint "eagle-import:R0402")
      (fields (field (name "MPN") "ERJ-2GEJ683X"))
      (libsource (lib "eagle-import") (part "R-US_R0402"))
    )
    (comp (ref "R8")
      (value "70k")
      (footprint "eagle-import:R0402")
      (fields (field (name "MPN") "ERJ-2GEJ683X"))
      (libsource (lib "eagle-import") (part "R-US_R0402"))
    )
    (comp (ref "R9")
      (value "70k")
      (footprint "eagle-import:R0402")
      (fields (field (name "MPN") "ERJ-2GEJ683X"))
      (libsource (lib "eagle-import") (part "R-US_R0402"))
    )
    (comp (ref "R10")
      (value "470")
      (footprint "eagle-import:R1206")
      (fields (field (name "MPN") "MCHP06W2F4700T5E"))
      (libsource (lib "eagle-import") (part "R-US_R1206"))
    )
    (comp (ref "R11")
      (value "470")
      (footprint "eagle-import:R1206")
      (fields (field (name "MPN") "MCHP06W2F4700T5E"))
      (libsource (lib "eagle-import") (part "R-US_R1206"))
    )
    (comp (ref "R12")
      (value "470")
      (footprint "eagle-import:R1206")
      (fields (field (name "MPN") "MCHP06W2F4700T5E"))
      (libsource (lib "eagle-import") (part "R-US_R1206"))
    )
    (comp (ref "R13")
      (value "70k")
      (footprint "eagle-import:R0402")
      (fields (field (name "MPN") "ERJ-2GEJ683X"))
      (libsource (lib "eagle-import") (part "R-US_R0402"))
    )
    (comp (ref "R14")
      (value "70k")
      (footprint "eagle-import:R0402")
      (fields (field (name "MPN") "ERJ-2GEJ683X"))
      (libsource (lib "eagle-import") (part "R-US_R0402"))
    )
    (comp (ref "R15")
      (value "70k")
      (footprint "eagle-import:R0402")
      (fields (field (name "MPN") "ERJ-2GEJ683X"))
      (libsource (lib "eagle-import") (part "R-US_R0402"))
    )
    (comp (ref "R16")
      (value "470")
      (footprint "eagle-import:R1206")
      (fields (field (name "MPN") "MCHP06W2F4700T5E"))
      (libsource (lib "eagle-import") (part "R-US_R1206"))
    )
    (comp (ref "R17")
      (value "470")
      (footprint "eagle-import:R1206")
      (fields (field (name "MPN") "MCHP06W2F4700T5E"))
      (libsource (lib "eagle-import") (part "R-US_R1206"))
    )
    (comp (ref "R18")
      (value "470")
      (footprint "eagle-import:R1206")
      (fields (field (name "MPN") "MCHP06W2F4700T5E"))
      (libsource (lib "eagle-import") (part "R-US_R1206"))
    )
    (comp (ref "R19")
      (value "70k")
      (footprint "eagle-import:R0402")
      (fields (field (name "MPN") "ERJ-2GEJ683X"))
      (libsource (lib "eagle-import") (part "R-US_R0402"))
    )
    (comp (ref "R20")
      (value "70k")
      (footprint "eagle-import:R0402")
      (fields (field (name "MPN") "ERJ-2GEJ683X"))
      (libsource (lib "eagle-import") (part "R-US_R0402"))
    )
    (comp (ref "R21")
      (value "70k")
      (footprint "eagle-import:R0402")
      (fields (field (name "MPN") "ERJ-2GEJ683X"))
      (libsource (lib "eagle-import") (part "R-US_R0402"))
    )
    (comp (ref "R22")
      (value "470")
      (footprint "eagle-import:R1206")
      (fields (field (name "MPN") "MCHP06W2F4700T5E"))
      (libsource (lib "eagle-import") (part "R-US_R1206"))
    )
    (comp (ref "R23")
      (value "470")
      (footprint "eagle-import:R1206")
      (fields (field (name "MPN") "MCHP06W2F4700T5E"))
      (libsource (lib "eagle-import") (part "R-US_R1206"))
    )
    (comp (ref "R24")
      (value "470")
      (footprint "eagle-import:R1206")
      (fields (field (name "MPN") "MCHP06W2F4700T5E"))
      (libsource (lib "eagle-import") (part "R-US_R1206"))
    )
    (comp (ref "R25")
      (value "70k")
      (footprint "eagle-import:R0402")
      (fields (field (name "MPN") "ERJ-2GEJ683X"))
      (libsource (lib "eagle-import") (part "R-US_R0402"))
    )
    (comp (ref "R26")
      (value "70k")
      (footprint "eagle-import:R0402")
      (fields (field (name "MPN") "ERJ-2GEJ683X"))
      (libsource (lib "eagle-import") (part "R-US_R0402"))
    )
    (comp (ref "R27")
      (value "70k")
      (footprint "eagle-import:R0402")
      (fields (field (name "MPN") "ERJ-2GEJ683X"))
      (libsource (lib "eagle-import") (part "R-US_R0402"))
    )
    (comp (ref "R28")
      (value "470")
      (footprint "eagle-import:R1206")
      (fields (field (name "MPN") "MCHP06W2F4700T5E"))
      (libsource (lib "eagle-import") (part "R-US_R1206"))
    )
    (comp (ref "R29")
      (value "470")
      (footprint "eagle-import:R1206")
      (fields (field (name "MPN") "MCHP06W2F4700T5E"))
      (libsource (lib "eagle-import") (part "R-US_R1206"))
    )
    (comp (ref "R30")
      (value "470")
      (footprint "eagle-import:R1206")
      (fields (field (name "MPN") "MCHP06W2F4700T5E"))
      (libsource (lib "eagle-import") (part "R-US_R1206"))
    )
    (comp (ref "R31")
      (value "70k")
      (footprint "eagle-import:R0402")
      (fields (field (name "MPN") "ERJ-2GEJ683X"))
      (libsource (lib "eagle-import") (part "R-US_R0402"))
    )
    (comp (ref "R32")
      (value "70k")
      (footprint "eagle-import:R0402")
      (fields (field (name "MPN") "ERJ-2GEJ683X"))
      (libsource (lib "eagle-import") (part "R-US_R0402"))
    )
    (comp (ref "R33")
      (value "70k")
      (footprint "eagle-import:R0402")
      (fields (field (name "MPN") "ERJ-2GEJ683X"))
      (libsource (lib "eagle-import") (part "R-US_R0402"))
    )
    (comp (ref "R34")
      (value "470")
      (footprint "eagle-import:R1206")
      (fields (field (name "MPN") "MCHP06W2F4700T5E"))
      (libsource (lib "eagle-import") (part "R-US_R1206"))
    )
    (comp (ref "R35")
      (value "470")
      (footprint "eagle-import:R1206")
      (fields (field (name "MPN") "MCHP06W2F4700T5E"))
      (libsource (lib "eagle-import") (part "R-US_R1206"))
    )
    (comp (ref "R36")
      (value "470")
      (footprint "eagle-import:R1206")
      (fields (field (name "MPN") "MCHP06W2F4700T5E"))
      (libsource (lib "eagle-import") (part "R-US_R1206"))
    )
    (comp (ref "R37")
      (value "70k")
      (footprint "eagle-import:R0402")
      (fields (field (name "MPN") "ERJ-2GEJ683X"))
      (libsource (lib "eagle-import") (part "R-US_R0402"))
    )
    (comp (ref "R38")
      (value "70k")
      (footprint "eagle-import:R0402")
      (fields (field (name "MPN") "ERJ-2GEJ683X"))
      (libsource (lib "eagle-import") (part "R-US_R0402"))
    )
    (comp (ref "R39")
      (value "70k")
      (footprint "eagle-import:R0402")
      (fields (field (name "MPN") "ERJ-2GEJ683X"))
      (libsource (lib "eagle-import") (part "R-US_R0402"))
    )
    (comp (ref "R40")
      (value "470")
      (footprint "eagle-import:R1206")
      (fields (field (name "MPN") "MCHP06W2F4700T5E"))
      (libsource (lib "eagle-import") (part "R-US_R1206"))
    )
    (comp (ref "R41")
      (value "470")
      (footprint "eagle-import:R1206")
      (fields (field (name "MPN") "MCHP06W2F4700T5E"))
      (libsource (lib "eagle-import") (part "R-US_R1206"))
    )
    (comp (ref "R42")
      (value "470")
      (footprint "eagle-import:R1206")
      (fields (field (name "MPN") "MCHP06W2F4700T5E"))
      (libsource (lib "eagle-import") (part "R-US_R1206"))
    )
    (comp (ref "R43")
      (value "70k")
      (footprint "eagle-import:R0402")
      (fields (field (name "MPN") "ERJ-2GEJ683X"))
      (libsource (lib "eagle-import") (part "R-US_R0402"))
    )
    (comp (ref "R44")
      (value "70k")
      (footprint "eagle-import:R0402")
      (fields (field (name "MPN") "ERJ-2GEJ683X"))
      (libsource (lib "eagle-import") (part "R-US_R0402"))
    )
    (comp (ref "R45")
      (value "70k")
      (footprint "eagle-import:R0402")
      (fields (field (name "MPN") "ERJ-2GEJ683X"))
      (libsource (lib "eagle-import") (part "R-US_R0402"))
    )
    (comp (ref "R46")
      (value "470")
      (footprint "eagle-import:R1206")
      (fields (field (name "MPN") "MCHP06W2F4700T5E"))
      (libsource (lib "eagle-import") (part "R-US_R1206"))
    )
    (comp (ref "R47")
      (value "470")
      (footprint "eagle-import:R1206")
      (fields (field (name "MPN") "MCHP06W2F4700T5E"))
      (libsource (lib "eagle-import") (part "R-US_R1206"))
    )
    (comp (ref "R48")
      (value "470")
      (footprint "eagle-import:R1206")
      (fields (field (name "MPN") "MCHP06W2F4700T5E"))
      (libsource (lib "eagle-import") (part "R-US_R1206"))
    )
    (comp (ref "R49")
      (value "10k")
      (footprint "eagle-import:R0402")
      (fields (field (name "MPN") "TNPW040210K0BEED"))
      (libsource (lib "eagle-import") (part "rcl_R-US_R0402"))
    )
    (comp (ref "R50")
      (value "470")
      (footprint "eagle-import:R0402")
      (fields (field (name "MPN") "ERJ-U02F4700X"))
      (libsource (lib "eagle-import") (part "rcl_R-US_R0402"))
    )
    (comp (ref "R51")
      (value "3.3k")
      (footprint "eagle-import:R0402")
      (fields (field (name "MPN") "M55342K11B3E30STIV"))
      (libsource (lib "eagle-import") (part "rcl_R-US_R0402"))
    )
  )
  (nets
    (net (code "1") (name "+5V") (class "Default")
      (node (ref "C26") (pin "1") (pinfunction "P$1_1") (pintype "passive"))
      (node (ref "C27") (pin "1") (pinfunction "P$1_1") (pintype "passive"))
      (node (ref "IC1") (pin "2") (pinfunction "VO_2") (pintype "passive"))
      (node (ref "IC2") (pin "32") (pinfunction "VCC_32") (pintype "power_in"))
      (node (ref "JP2") (pin "1") (pinfunction "1_1") (pintype "passive"))
      (node (ref "LED25") (pin "A") (pinfunction "A_A") (pintype "passive"))
      (node (ref "R49") (pin "2") (pinfunction "2_2") (pintype "passive"))
    )
    (net (code "2") (name "+12V") (class "Default")
      (node (ref "2.1MM1") (pin "TIP") (pinfunction "TIP_TIP") (pintype "bidirectional"))
      (node (ref "C25") (pin "1") (pinfunction "P$1_1") (pintype "passive"))
      (node (ref "IC1") (pin "1") (pinfunction "VIN_1") (pintype "input"))
      (node (ref "JP1") (pin "1") (pinfunction "1_1") (pintype "passive"))
      (node (ref "LED1") (pin "A") (pinfunction "A_A") (pintype "passive"))
      (node (ref "LED10") (pin "A") (pinfunction "A_A") (pintype "passive"))
      (node (ref "LED11") (pin "A") (pinfunction "A_A") (pintype "passive"))
      (node (ref "LED12") (pin "A") (pinfunction "A_A") (pintype "passive"))
      (node (ref "LED13") (pin "A") (pinfunction "A_A") (pintype "passive"))
      (node (ref "LED14") (pin "A") (pinfunction "A_A") (pintype "passive"))
      (node (ref "LED15") (pin "A") (pinfunction "A_A") (pintype "passive"))
      (node (ref "LED16") (pin "A") (pinfunction "A_A") (pintype "passive"))
      (node (ref "LED17") (pin "A") (pinfunction "A_A") (pintype "passive"))
      (node (ref "LED18") (pin "A") (pinfunction "A_A") (pintype "passive"))
      (node (ref "LED19") (pin "A") (pinfunction "A_A") (pintype "passive"))
      (node (ref "LED2") (pin "A") (pinfunction "A_A") (pintype "passive"))
      (node (ref "LED20") (pin "A") (pinfunction "A_A") (pintype "passive"))
      (node (ref "LED21") (pin "A") (pinfunction "A_A") (pintype "passive"))
      (node (ref "LED22") (pin "A") (pinfunction "A_A") (pintype "passive"))
      (node (ref "LED23") (pin "A") (pinfunction "A_A") (pintype "passive"))
      (node (ref "LED24") (pin "A") (pinfunction "A_A") (pintype "passive"))
      (node (ref "LED3") (pin "A") (pinfunction "A_A") (pintype "passive"))
      (node (ref "LED4") (pin "A") (pinfunction "A_A") (pintype "passive"))
      (node (ref "LED5") (pin "A") (pinfunction "A_A") (pintype "passive"))
      (node (ref "LED6") (pin "A") (pinfunction "A_A") (pintype "passive"))
      (node (ref "LED7") (pin "A") (pinfunction "A_A") (pintype "passive"))
      (node (ref "LED8") (pin "A") (pinfunction "A_A") (pintype "passive"))
      (node (ref "LED9") (pin "A") (pinfunction "A_A") (pintype "passive"))
      (node (ref "Q1") (pin "2") (pinfunction "S_2") (pintype "passive"))
      (node (ref "Q10") (pin "2") (pinfunction "S_2") (pintype "passive"))
      (node (ref "Q11") (pin "2") (pinfunction "S_2") (pintype "passive"))
      (node (ref "Q12") (pin "2") (pinfunction "S_2") (pintype "passive"))
      (node (ref "Q13") (pin "2") (pinfunction "S_2") (pintype "passive"))
      (node (ref "Q14") (pin "2") (pinfunction "S_2") (pintype "passive"))
      (node (ref "Q15") (pin "2") (pinfunction "S_2") (pintype "passive"))
      (node (ref "Q16") (pin "2") (pinfunction "S_2") (pintype "passive"))
      (node (ref "Q17") (pin "2") (pinfunction "S_2") (pintype "passive"))
      (node (ref "Q18") (pin "2") (pinfunction "S_2") (pintype "passive"))
      (node (ref "Q19") (pin "2") (pinfunction "S_2") (pintype "passive"))
      (node (ref "Q2") (pin "2") (pinfunction "S_2") (pintype "passive"))
      (node (ref "Q20") (pin "2") (pinfunction "S_2") (pintype "passive"))
      (node (ref "Q21") (pin "2") (pinfunction "S_2") (pintype "passive"))
      (node (ref "Q22") (pin "2") (pinfunction "S_2") (pintype "passive"))
      (node (ref "Q23") (pin "2") (pinfunction "S_2") (pintype "passive"))
      (node (ref "Q24") (pin "2") (pinfunction "S_2") (pintype "passive"))
      (node (ref "Q3") (pin "2") (pinfunction "S_2") (pintype "passive"))
      (node (ref "Q4") (pin "2") (pinfunction "S_2") (pintype "passive"))
      (node (ref "Q5") (pin "2") (pinfunction "S_2") (pintype "passive"))
      (node (ref "Q6") (pin "2") (pinfunction "S_2") (pintype "passive"))
      (node (ref "Q7") (pin "2") (pinfunction "S_2") (pintype "passive"))
      (node (ref "Q8") (pin "2") (pinfunction "S_2") (pintype "passive"))
      (node (ref "Q9") (pin "2") (pinfunction "S_2") (pintype "passive"))
      (node (ref "R1") (pin "2") (pinfunction "2_2") (pintype "passive"))
      (node (ref "R13") (pin "2") (pinfunction "2_2") (pintype "passive"))
      (node (ref "R14") (pin "2") (pinfunction "2_2") (pintype "passive"))
      (node (ref "R15") (pin "2") (pinfunction "2_2") (pintype "passive"))
      (node (ref "R19") (pin "2") (pinfunction "2_2") (pintype "passive"))
      (node (ref "R2") (pin "2") (pinfunction "2_2") (pintype "passive"))
      (node (ref "R20") (pin "2") (pinfunction "2_2") (pintype "passive"))
      (node (ref "R21") (pin "2") (pinfunction "2_2") (pintype "passive"))
      (node (ref "R25") (pin "2") (pinfunction "2_2") (pintype "passive"))
      (node (ref "R26") (pin "2") (pinfunction "2_2") (pintype "passive"))
      (node (ref "R27") (pin "2") (pinfunction "2_2") (pintype "passive"))
      (node (ref "R3") (pin "2") (pinfunction "2_2") (pintype "passive"))
      (node (ref "R31") (pin "2") (pinfunction "2_2") (pintype "passive"))
      (node (ref "R32") (pin "2") (pinfunction "2_2") (pintype "passive"))
      (node (ref "R33") (pin "2") (pinfunction "2_2") (pintype "passive"))
      (node (ref "R37") (pin "2") (pinfunction "2_2") (pintype "passive"))
      (node (ref "R38") (pin "2") (pinfunction "2_2") (pintype "passive"))
      (node (ref "R39") (pin "2") (pinfunction "2_2") (pintype "passive"))
      (node (ref "R43") (pin "2") (pinfunction "2_2") (pintype "passive"))
      (node (ref "R44") (pin "2") (pinfunction "2_2") (pintype "passive"))
      (node (ref "R45") (pin "2") (pinfunction "2_2") (pintype "passive"))
      (node (ref "R7") (pin "2") (pinfunction "2_2") (pintype "passive"))
      (node (ref "R8") (pin "2") (pinfunction "2_2") (pintype "passive"))
      (node (ref "R9") (pin "2") (pinfunction "2_2") (pintype "passive"))
    )
    (net (code "3") (name "/BLANK") (class "Default")
      (node (ref "CN1") (pin "4") (pinfunction "4_4") (pintype "bidirectional"))
      (node (ref "IC2") (pin "2") (pinfunction "BLANK_2") (pintype "input"))
      (node (ref "IC2") (pin "30") (pinfunction "XLAT_30") (pintype "input"))
      (node (ref "R49") (pin "1") (pinfunction "1_1") (pintype "passive"))
    )
    (net (code "4") (name "/OUT0") (class "Default")
      (node (ref "IC2") (pin "5") (pinfunction "OUT0_5") (pintype "open_collector"))
      (node (ref "Q1") (pin "1") (pinfunction "G_1") (pintype "passive"))
      (node (ref "R1") (pin "1") (pinfunction "1_1") (pintype "passive"))
      (node (ref "R4") (pin "1") (pinfunction "1_1") (pintype "passive"))
    )
    (net (code "5") (name "/OUT1") (class "Default")
      (node (ref "IC2") (pin "6") (pinfunction "OUT1_6") (pintype "open_collector"))
      (node (ref "Q2") (pin "1") (pinfunction "G_1") (pintype "passive"))
      (node (ref "R2") (pin "1") (pinfunction "1_1") (pintype "passive"))
      (node (ref "R5") (pin "1") (pinfunction "1_1") (pintype "passive"))
    )
    (net (code "6") (name "/OUT2") (class "Default")
      (node (ref "IC2") (pin "7") (pinfunction "OUT2_7") (pintype "open_collector"))
      (node (ref "Q3") (pin "1") (pinfunction "G_1") (pintype "passive"))
      (node (ref "R3") (pin "1") (pinfunction "1_1") (pintype "passive"))
      (node (ref "R6") (pin "1") (pinfunction "1_1") (pintype "passive"))
    )
    (net (code "7") (name "/OUT3") (class "Default")
      (node (ref "IC2") (pin "8") (pinfunction "OUT3_8") (pintype "open_collector"))
      (node (ref "Q4") (pin "1") (pinfunction "G_1") (pintype "passive"))
      (node (ref "R10") (pin "1") (pinfunction "1_1") (pintype "passive"))
      (node (ref "R7") (pin "1") (pinfunction "1_1") (pintype "passive"))
    )
    (net (code "8") (name "/OUT4") (class "Default")
      (node (ref "IC2") (pin "9") (pinfunction "OUT4_9") (pintype "open_collector"))
      (node (ref "Q5") (pin "1") (pinfunction "G_1") (pintype "passive"))
      (node (ref "R11") (pin "1") (pinfunction "1_1") (pintype "passive"))
      (node (ref "R8") (pin "1") (pinfunction "1_1") (pintype "passive"))
    )
    (net (code "9") (name "/OUT5") (class "Default")
      (node (ref "IC2") (pin "10") (pinfunction "OUT5_10") (pintype "open_collector"))
      (node (ref "Q6") (pin "1") (pinfunction "G_1") (pintype "passive"))
      (node (ref "R12") (pin "1") (pinfunction "1_1") (pintype "passive"))
      (node (ref "R9") (pin "1") (pinfunction "1_1") (pintype "passive"))
    )
    (net (code "10") (name "/OUT6") (class "Default")
      (node (ref "IC2") (pin "11") (pinfunction "OUT6_11") (pintype "open_collector"))
      (node (ref "Q7") (pin "1") (pinfunction "G_1") (pintype "passive"))
      (node (ref "R13") (pin "1") (pinfunction "1_1") (pintype "passive"))
      (node (ref "R16") (pin "1") (pinfunction "1_1") (pintype "passive"))
    )
    (net (code "11") (name "/OUT7") (class "Default")
      (node (ref "IC2") (pin "12") (pinfunction "OUT7_12") (pintype "open_collector"))
      (node (ref "Q8") (pin "1") (pinfunction "G_1") (pintype "passive"))
      (node (ref "R14") (pin "1") (pinfunction "1_1") (pintype "passive"))
      (node (ref "R17") (pin "1") (pinfunction "1_1") (pintype "passive"))
    )
    (net (code "12") (name "/OUT8") (class "Default")
      (node (ref "IC2") (pin "13") (pinfunction "OUT8_13") (pintype "open_collector"))
      (node (ref "Q9") (pin "1") (pinfunction "G_1") (pintype "passive"))
      (node (ref "R15") (pin "1") (pinfunction "1_1") (pintype "passive"))
      (node (ref "R18") (pin "1") (pinfunction "1_1") (pintype "passive"))
    )
    (net (code "13") (name "/OUT9") (class "Default")
      (node (ref "IC2") (pin "14") (pinfunction "OUT9_14") (pintype "open_collector"))
      (node (ref "Q10") (pin "1") (pinfunction "G_1") (pintype "passive"))
      (node (ref "R19") (pin "1") (pinfunction "1_1") (pintype "passive"))
      (node (ref "R22") (pin "1") (pinfunction "1_1") (pintype "passive"))
    )
    (net (code "14") (name "/OUT10") (class "Default")
      (node (ref "IC2") (pin "15") (pinfunction "OUT10_15") (pintype "open_collector"))
      (node (ref "Q11") (pin "1") (pinfunction "G_1") (pintype "passive"))
      (node (ref "R20") (pin "1") (pinfunction "1_1") (pintype "passive"))
      (node (ref "R23") (pin "1") (pinfunction "1_1") (pintype "passive"))
    )
    (net (code "15") (name "/OUT11") (class "Default")
      (node (ref "IC2") (pin "16") (pinfunction "OUT11_16") (pintype "open_collector"))
      (node (ref "Q12") (pin "1") (pinfunction "G_1") (pintype "passive"))
      (node (ref "R21") (pin "1") (pinfunction "1_1") (pintype "passive"))
      (node (ref "R24") (pin "1") (pinfunction "1_1") (pintype "passive"))
    )
    (net (code "16") (name "/OUT12") (class "Default")
      (node (ref "IC2") (pin "17") (pinfunction "OUT12_17") (pintype "open_collector"))
      (node (ref "Q13") (pin "1") (pinfunction "G_1") (pintype "passive"))
      (node (ref "R25") (pin "1") (pinfunction "1_1") (pintype "passive"))
      (node (ref "R28") (pin "1") (pinfunction "1_1") (pintype "passive"))
    )
    (net (code "17") (name "/OUT13") (class "Default")
      (node (ref "IC2") (pin "18") (pinfunction "OUT13_18") (pintype "open_collector"))
      (node (ref "Q14") (pin "1") (pinfunction "G_1") (pintype "passive"))
      (node (ref "R26") (pin "1") (pinfunction "1_1") (pintype "passive"))
      (node (ref "R29") (pin "1") (pinfunction "1_1") (pintype "passive"))
    )
    (net (code "18") (name "/OUT14") (class "Default")
      (node (ref "IC2") (pin "19") (pinfunction "OUT14_19") (pintype "open_collector"))
      (node (ref "Q15") (pin "1") (pinfunction "G_1") (pintype "passive"))
      (node (ref "R27") (pin "1") (pinfunction "1_1") (pintype "passive"))
      (node (ref "R30") (pin "1") (pinfunction "1_1") (pintype "passive"))
    )
    (net (code "19") (name "/OUT15") (class "Default")
      (node (ref "IC2") (pin "20") (pinfunction "OUT15_20") (pintype "open_collector"))
      (node (ref "Q16") (pin "1") (pinfunction "G_1") (pintype "passive"))
      (node (ref "R31") (pin "1") (pinfunction "1_1") (pintype "passive"))
      (node (ref "R34") (pin "1") (pinfunction "1_1") (pintype "passive"))
    )
    (net (code "20") (name "/OUT16") (class "Default")
      (node (ref "IC2") (pin "21") (pinfunction "OUT16_21") (pintype "open_collector"))
      (node (ref "Q17") (pin "1") (pinfunction "G_1") (pintype "passive"))
      (node (ref "R32") (pin "1") (pinfunction "1_1") (pintype "passive"))
      (node (ref "R35") (pin "1") (pinfunction "1_1") (pintype "passive"))
    )
    (net (code "21") (name "/OUT17") (class "Default")
      (node (ref "IC2") (pin "22") (pinfunction "OUT17_22") (pintype "open_collector"))
      (node (ref "Q18") (pin "1") (pinfunction "G_1") (pintype "passive"))
      (node (ref "R33") (pin "1") (pinfunction "1_1") (pintype "passive"))
      (node (ref "R36") (pin "1") (pinfunction "1_1") (pintype "passive"))
    )
    (net (code "22") (name "/OUT18") (class "Default")
      (node (ref "IC2") (pin "23") (pinfunction "OUT18_23") (pintype "open_collector"))
      (node (ref "Q19") (pin "1") (pinfunction "G_1") (pintype "passive"))
      (node (ref "R37") (pin "1") (pinfunction "1_1") (pintype "passive"))
      (node (ref "R40") (pin "1") (pinfunction "1_1") (pintype "passive"))
    )
    (net (code "23") (name "/OUT19") (class "Default")
      (node (ref "IC2") (pin "24") (pinfunction "OUT19_24") (pintype "open_collector"))
      (node (ref "Q20") (pin "1") (pinfunction "G_1") (pintype "passive"))
      (node (ref "R38") (pin "1") (pinfunction "1_1") (pintype "passive"))
      (node (ref "R41") (pin "1") (pinfunction "1_1") (pintype "passive"))
    )
    (net (code "24") (name "/OUT20") (class "Default")
      (node (ref "IC2") (pin "25") (pinfunction "OUT20_25") (pintype "open_collector"))
      (node (ref "Q21") (pin "1") (pinfunction "G_1") (pintype "passive"))
      (node (ref "R39") (pin "1") (pinfunction "1_1") (pintype "passive"))
      (node (ref "R42") (pin "1") (pinfunction "1_1") (pintype "passive"))
    )
    (net (code "25") (name "/OUT21") (class "Default")
      (node (ref "IC2") (pin "26") (pinfunction "OUT21_26") (pintype "open_collector"))
      (node (ref "Q22") (pin "1") (pinfunction "G_1") (pintype "passive"))
      (node (ref "R43") (pin "1") (pinfunction "1_1") (pintype "passive"))
      (node (ref "R46") (pin "1") (pinfunction "1_1") (pintype "passive"))
    )
    (net (code "26") (name "/OUT22") (class "Default")
      (node (ref "IC2") (pin "27") (pinfunction "OUT22_27") (pintype "open_collector"))
      (node (ref "Q23") (pin "1") (pinfunction "G_1") (pintype "passive"))
      (node (ref "R44") (pin "1") (pinfunction "1_1") (pintype "passive"))
      (node (ref "R47") (pin "1") (pinfunction "1_1") (pintype "passive"))
    )
    (net (code "27") (name "/OUT23") (class "Default")
      (node (ref "IC2") (pin "28") (pinfunction "OUT23_28") (pintype "open_collector"))
      (node (ref "Q24") (pin "1") (pinfunction "G_1") (pintype "passive"))
      (node (ref "R45") (pin "1") (pinfunction "1_1") (pintype "passive"))
      (node (ref "R48") (pin "1") (pinfunction "1_1") (pintype "passive"))
    )
    (net (code "28") (name "/SCLK") (class "Default")
      (node (ref "CN1") (pin "3") (pinfunction "3_3") (pintype "bidirectional"))
      (node (ref "IC2") (pin "3") (pinfunction "SCLK_3") (pintype "input"))
    )
    (net (code "29") (name "/SIN") (class "Default")
      (node (ref "CN1") (pin "2") (pinfunction "2_2") (pintype "bidirectional"))
      (node (ref "IC2") (pin "4") (pinfunction "SIN_4") (pintype "input"))
    )
    (net (code "30") (name "GND") (class "Default")
      (node (ref "2.1MM1") (pin "RING") (pinfunction "RING_RING") (pintype "bidirectional"))
      (node (ref "2.1MM1") (pin "RING_SW") (pinfunction "RING_SW_RING_SW") (pintype "bidirectional"))
      (node (ref "C1") (pin "2") (pinfunction "2_2") (pintype "passive"))
      (node (ref "C10") (pin "2") (pinfunction "2_2") (pintype "passive"))
      (node (ref "C11") (pin "2") (pinfunction "2_2") (pintype "passive"))
      (node (ref "C12") (pin "2") (pinfunction "2_2") (pintype "passive"))
      (node (ref "C13") (pin "2") (pinfunction "2_2") (pintype "passive"))
      (node (ref "C14") (pin "2") (pinfunction "2_2") (pintype "passive"))
      (node (ref "C15") (pin "2") (pinfunction "2_2") (pintype "passive"))
      (node (ref "C16") (pin "2") (pinfunction "2_2") (pintype "passive"))
      (node (ref "C17") (pin "2") (pinfunction "2_2") (pintype "passive"))
      (node (ref "C18") (pin "2") (pinfunction "2_2") (pintype "passive"))
      (node (ref "C19") (pin "2") (pinfunction "2_2") (pintype "passive"))
      (node (ref "C2") (pin "2") (pinfunction "2_2") (pintype "passive"))
      (node (ref "C20") (pin "2") (pinfunction "2_2") (pintype "passive"))
      (node (ref "C21") (pin "2") (pinfunction "2_2") (pintype "passive"))
      (node (ref "C22") (pin "2") (pinfunction "2_2") (pintype "passive"))
      (node (ref "C23") (pin "2") (pinfunction "2_2") (pintype "passive"))
      (node (ref "C24") (pin "2") (pinfunction "2_2") (pintype "passive"))
      (node (ref "C25") (pin "2") (pinfunction "P$2_2") (pintype "passive"))
      (node (ref "C26") (pin "2") (pinfunction "P$2_2") (pintype "passive"))
      (node (ref "C27") (pin "2") (pinfunction "P$2_2") (pintype "passive"))
      (node (ref "C3") (pin "2") (pinfunction "2_2") (pintype "passive"))
      (node (ref "C4") (pin "2") (pinfunction "2_2") (pintype "passive"))
      (node (ref "C5") (pin "2") (pinfunction "2_2") (pintype "passive"))
      (node (ref "C6") (pin "2") (pinfunction "2_2") (pintype "passive"))
      (node (ref "C7") (pin "2") (pinfunction "2_2") (pintype "passive"))
      (node (ref "C8") (pin "2") (pinfunction "2_2") (pintype "passive"))
      (node (ref "C9") (pin "2") (pinfunction "2_2") (pintype "passive"))
      (node (ref "CN1") (pin "1") (pinfunction "1_1") (pintype "bidirectional"))
      (node (ref "D1") (pin "1") (pinfunction "A_1") (pintype "passive"))
      (node (ref "D10") (pin "1") (pinfunction "A_1") (pintype "passive"))
      (node (ref "D11") (pin "1") (pinfunction "A_1") (pintype "passive"))
      (node (ref "D12") (pin "1") (pinfunction "A_1") (pintype "passive"))
      (node (ref "D13") (pin "1") (pinfunction "A_1") (pintype "passive"))
      (node (ref "D14") (pin "1") (pinfunction "A_1") (pintype "passive"))
      (node (ref "D15") (pin "1") (pinfunction "A_1") (pintype "passive"))
      (node (ref "D16") (pin "1") (pinfunction "A_1") (pintype "passive"))
      (node (ref "D17") (pin "1") (pinfunction "A_1") (pintype "passive"))
      (node (ref "D18") (pin "1") (pinfunction "A_1") (pintype "passive"))
      (node (ref "D19") (pin "1") (pinfunction "A_1") (pintype "passive"))
      (node (ref "D2") (pin "1") (pinfunction "A_1") (pintype "passive"))
      (node (ref "D20") (pin "1") (pinfunction "A_1") (pintype "passive"))
      (node (ref "D21") (pin "1") (pinfunction "A_1") (pintype "passive"))
      (node (ref "D22") (pin "1") (pinfunction "A_1") (pintype "passive"))
      (node (ref "D23") (pin "1") (pinfunction "A_1") (pintype "passive"))
      (node (ref "D24") (pin "1") (pinfunction "A_1") (pintype "passive"))
      (node (ref "D3") (pin "1") (pinfunction "A_1") (pintype "passive"))
      (node (ref "D4") (pin "1") (pinfunction "A_1") (pintype "passive"))
      (node (ref "D5") (pin "1") (pinfunction "A_1") (pintype "passive"))
      (node (ref "D6") (pin "1") (pinfunction "A_1") (pintype "passive"))
      (node (ref "D7") (pin "1") (pinfunction "A_1") (pintype "passive"))
      (node (ref "D8") (pin "1") (pinfunction "A_1") (pintype "passive"))
      (node (ref "D9") (pin "1") (pinfunction "A_1") (pintype "passive"))
      (node (ref "IC1") (pin "3") (pinfunction "GND_3") (pintype "passive"))
      (node (ref "IC2") (pin "1") (pinfunction "GND_1") (pintype "power_in"))
      (node (ref "IC2") (pin "EXP") (pinfunction "PAD_EXP") (pintype "passive"))
      (node (ref "M0") (pin "2") (pinfunction "2_2") (pintype "passive"))
      (node (ref "M1") (pin "2") (pinfunction "2_2") (pintype "passive"))
      (node (ref "M10") (pin "2") (pinfunction "2_2") (pintype "passive"))
      (node (ref "M11") (pin "2") (pinfunction "2_2") (pintype "passive"))
      (node (ref "M12") (pin "2") (pinfunction "2_2") (pintype "passive"))
      (node (ref "M13") (pin "2") (pinfunction "2_2") (pintype "passive"))
      (node (ref "M14") (pin "2") (pinfunction "2_2") (pintype "passive"))
      (node (ref "M15") (pin "2") (pinfunction "2_2") (pintype "passive"))
      (node (ref "M16") (pin "2") (pinfunction "2_2") (pintype "passive"))
      (node (ref "M17") (pin "2") (pinfunction "2_2") (pintype "passive"))
      (node (ref "M18") (pin "2") (pinfunction "2_2") (pintype "passive"))
      (node (ref "M19") (pin "2") (pinfunction "2_2") (pintype "passive"))
      (node (ref "M2") (pin "2") (pinfunction "2_2") (pintype "passive"))
      (node (ref "M20") (pin "2") (pinfunction "2_2") (pintype "passive"))
      (node (ref "M21") (pin "2") (pinfunction "2_2") (pintype "passive"))
      (node (ref "M22") (pin "2") (pinfunction "2_2") (pintype "passive"))
      (node (ref "M23") (pin "2") (pinfunction "2_2") (pintype "passive"))
      (node (ref "M3") (pin "2") (pinfunction "2_2") (pintype "passive"))
      (node (ref "M4") (pin "2") (pinfunction "2_2") (pintype "passive"))
      (node (ref "M5") (pin "2") (pinfunction "2_2") (pintype "passive"))
      (node (ref "M6") (pin "2") (pinfunction "2_2") (pintype "passive"))
      (node (ref "M7") (pin "2") (pinfunction "2_2") (pintype "passive"))
      (node (ref "M8") (pin "2") (pinfunction "2_2") (pintype "passive"))
      (node (ref "M9") (pin "2") (pinfunction "2_2") (pintype "passive"))
      (node (ref "R50") (pin "1") (pinfunction "1_1") (pintype "passive"))
      (node (ref "R51") (pin "2") (pinfunction "2_2") (pintype "passive"))
    )
    (net (code "31") (name "Net-(D1-C)") (class "Default")
      (node (ref "C1") (pin "1") (pinfunction "1_1") (pintype "passive"))
      (node (ref "D1") (pin "3") (pinfunction "C_3") (pintype "passive"))
      (node (ref "M0") (pin "1") (pinfunction "1_1") (pintype "passive"))
      (node (ref "Q1") (pin "3") (pinfunction "D_3") (pintype "passive"))
    )
    (net (code "32") (name "Net-(D2-C)") (class "Default")
      (node (ref "C2") (pin "1") (pinfunction "1_1") (pintype "passive"))
      (node (ref "D2") (pin "3") (pinfunction "C_3") (pintype "passive"))
      (node (ref "M1") (pin "1") (pinfunction "1_1") (pintype "passive"))
      (node (ref "Q2") (pin "3") (pinfunction "D_3") (pintype "passive"))
    )
    (net (code "33") (name "Net-(D3-C)") (class "Default")
      (node (ref "C3") (pin "1") (pinfunction "1_1") (pintype "passive"))
      (node (ref "D3") (pin "3") (pinfunction "C_3") (pintype "passive"))
      (node (ref "M2") (pin "1") (pinfunction "1_1") (pintype "passive"))
      (node (ref "Q3") (pin "3") (pinfunction "D_3") (pintype "passive"))
    )
    (net (code "34") (name "Net-(D4-C)") (class "Default")
      (node (ref "C4") (pin "1") (pinfunction "1_1") (pintype "passive"))
      (node (ref "D4") (pin "3") (pinfunction "C_3") (pintype "passive"))
      (node (ref "M3") (pin "1") (pinfunction "1_1") (pintype "passive"))
      (node (ref "Q4") (pin "3") (pinfunction "D_3") (pintype "passive"))
    )
    (net (code "35") (name "Net-(D5-C)") (class "Default")
      (node (ref "C5") (pin "1") (pinfunction "1_1") (pintype "passive"))
      (node (ref "D5") (pin "3") (pinfunction "C_3") (pintype "passive"))
      (node (ref "M4") (pin "1") (pinfunction "1_1") (pintype "passive"))
      (node (ref "Q5") (pin "3") (pinfunction "D_3") (pintype "passive"))
    )
    (net (code "36") (name "Net-(D6-C)") (class "Default")
      (node (ref "C6") (pin "1") (pinfunction "1_1") (pintype "passive"))
      (node (ref "D6") (pin "3") (pinfunction "C_3") (pintype "passive"))
      (node (ref "M5") (pin "1") (pinfunction "1_1") (pintype "passive"))
      (node (ref "Q6") (pin "3") (pinfunction "D_3") (pintype "passive"))
    )
    (net (code "37") (name "Net-(D7-C)") (class "Default")
      (node (ref "C7") (pin "1") (pinfunction "1_1") (pintype "passive"))
      (node (ref "D7") (pin "3") (pinfunction "C_3") (pintype "passive"))
      (node (ref "M6") (pin "1") (pinfunction "1_1") (pintype "passive"))
      (node (ref "Q7") (pin "3") (pinfunction "D_3") (pintype "passive"))
    )
    (net (code "38") (name "Net-(D8-C)") (class "Default")
      (node (ref "C8") (pin "1") (pinfunction "1_1") (pintype "passive"))
      (node (ref "D8") (pin "3") (pinfunction "C_3") (pintype "passive"))
      (node (ref "M7") (pin "1") (pinfunction "1_1") (pintype "passive"))
      (node (ref "Q8") (pin "3") (pinfunction "D_3") (pintype "passive"))
    )
    (net (code "39") (name "Net-(D9-C)") (class "Default")
      (node (ref "C9") (pin "1") (pinfunction "1_1") (pintype "passive"))
      (node (ref "D9") (pin "3") (pinfunction "C_3") (pintype "passive"))
      (node (ref "M8") (pin "1") (pinfunction "1_1") (pintype "passive"))
      (node (ref "Q9") (pin "3") (pinfunction "D_3") (pintype "passive"))
    )
    (net (code "40") (name "Net-(D10-C)") (class "Default")
      (node (ref "C10") (pin "1") (pinfunction "1_1") (pintype "passive"))
      (node (ref "D10") (pin "3") (pinfunction "C_3") (pintype "passive"))
      (node (ref "M9") (pin "1") (pinfunction "1_1") (pintype "passive"))
      (node (ref "Q10") (pin "3") (pinfunction "D_3") (pintype "passive"))
    )
    (net (code "41") (name "Net-(D11-C)") (class "Default")
      (node (ref "C11") (pin "1") (pinfunction "1_1") (pintype "passive"))
      (node (ref "D11") (pin "3") (pinfunction "C_3") (pintype "passive"))
      (node (ref "M10") (pin "1") (pinfunction "1_1") (pintype "passive"))
      (node (ref "Q11") (pin "3") (pinfunction "D_3") (pintype "passive"))
    )
    (net (code "42") (name "Net-(D12-C)") (class "Default")
      (node (ref "C12") (pin "1") (pinfunction "1_1") (pintype "passive"))
      (node (ref "D12") (pin "3") (pinfunction "C_3") (pintype "passive"))
      (node (ref "M11") (pin "1") (pinfunction "1_1") (pintype "passive"))
      (node (ref "Q12") (pin "3") (pinfunction "D_3") (pintype "passive"))
    )
    (net (code "43") (name "Net-(D13-C)") (class "Default")
      (node (ref "C13") (pin "1") (pinfunction "1_1") (pintype "passive"))
      (node (ref "D13") (pin "3") (pinfunction "C_3") (pintype "passive"))
      (node (ref "M12") (pin "1") (pinfunction "1_1") (pintype "passive"))
      (node (ref "Q13") (pin "3") (pinfunction "D_3") (pintype "passive"))
    )
    (net (code "44") (name "Net-(D14-C)") (class "Default")
      (node (ref "C14") (pin "1") (pinfunction "1_1") (pintype "passive"))
      (node (ref "D14") (pin "3") (pinfunction "C_3") (pintype "passive"))
      (node (ref "M13") (pin "1") (pinfunction "1_1") (pintype "passive"))
      (node (ref "Q14") (pin "3") (pinfunction "D_3") (pintype "passive"))
    )
    (net (code "45") (name "Net-(D15-C)") (class "Default")
      (node (ref "C15") (pin "1") (pinfunction "1_1") (pintype "passive"))
      (node (ref "D15") (pin "3") (pinfunction "C_3") (pintype "passive"))
      (node (ref "M14") (pin "1") (pinfunction "1_1") (pintype "passive"))
      (node (ref "Q15") (pin "3") (pinfunction "D_3") (pintype "passive"))
    )
    (net (code "46") (name "Net-(D16-C)") (class "Default")
      (node (ref "C16") (pin "1") (pinfunction "1_1") (pintype "passive"))
      (node (ref "D16") (pin "3") (pinfunction "C_3") (pintype "passive"))
      (node (ref "M15") (pin "1") (pinfunction "1_1") (pintype "passive"))
      (node (ref "Q16") (pin "3") (pinfunction "D_3") (pintype "passive"))
    )
    (net (code "47") (name "Net-(D17-C)") (class "Default")
      (node (ref "C17") (pin "1") (pinfunction "1_1") (pintype "passive"))
      (node (ref "D17") (pin "3") (pinfunction "C_3") (pintype "passive"))
      (node (ref "M16") (pin "1") (pinfunction "1_1") (pintype "passive"))
      (node (ref "Q17") (pin "3") (pinfunction "D_3") (pintype "passive"))
    )
    (net (code "48") (name "Net-(D18-C)") (class "Default")
      (node (ref "C18") (pin "1") (pinfunction "1_1") (pintype "passive"))
      (node (ref "D18") (pin "3") (pinfunction "C_3") (pintype "passive"))
      (node (ref "M17") (pin "1") (pinfunction "1_1") (pintype "passive"))
      (node (ref "Q18") (pin "3") (pinfunction "D_3") (pintype "passive"))
    )
    (net (code "49") (name "Net-(D19-C)") (class "Default")
      (node (ref "C19") (pin "1") (pinfunction "1_1") (pintype "passive"))
      (node (ref "D19") (pin "3") (pinfunction "C_3") (pintype "passive"))
      (node (ref "M18") (pin "1") (pinfunction "1_1") (pintype "passive"))
      (node (ref "Q19") (pin "3") (pinfunction "D_3") (pintype "passive"))
    )
    (net (code "50") (name "Net-(D20-C)") (class "Default")
      (node (ref "C20") (pin "1") (pinfunction "1_1") (pintype "passive"))
      (node (ref "D20") (pin "3") (pinfunction "C_3") (pintype "passive"))
      (node (ref "M19") (pin "1") (pinfunction "1_1") (pintype "passive"))
      (node (ref "Q20") (pin "3") (pinfunction "D_3") (pintype "passive"))
    )
    (net (code "51") (name "Net-(D21-C)") (class "Default")
      (node (ref "C21") (pin "1") (pinfunction "1_1") (pintype "passive"))
      (node (ref "D21") (pin "3") (pinfunction "C_3") (pintype "passive"))
      (node (ref "M20") (pin "1") (pinfunction "1_1") (pintype "passive"))
      (node (ref "Q21") (pin "3") (pinfunction "D_3") (pintype "passive"))
    )
    (net (code "52") (name "Net-(D22-C)") (class "Default")
      (node (ref "C22") (pin "1") (pinfunction "1_1") (pintype "passive"))
      (node (ref "D22") (pin "3") (pinfunction "C_3") (pintype "passive"))
      (node (ref "M21") (pin "1") (pinfunction "1_1") (pintype "passive"))
      (node (ref "Q22") (pin "3") (pinfunction "D_3") (pintype "passive"))
    )
    (net (code "53") (name "Net-(D23-C)") (class "Default")
      (node (ref "C23") (pin "1") (pinfunction "1_1") (pintype "passive"))
      (node (ref "D23") (pin "3") (pinfunction "C_3") (pintype "passive"))
      (node (ref "M22") (pin "1") (pinfunction "1_1") (pintype "passive"))
      (node (ref "Q23") (pin "3") (pinfunction "D_3") (pintype "passive"))
    )
    (net (code "54") (name "Net-(D24-C)") (class "Default")
      (node (ref "C24") (pin "1") (pinfunction "1_1") (pintype "passive"))
      (node (ref "D24") (pin "3") (pinfunction "C_3") (pintype "passive"))
      (node (ref "M23") (pin "1") (pinfunction "1_1") (pintype "passive"))
      (node (ref "Q24") (pin "3") (pinfunction "D_3") (pintype "passive"))
    )
    (net (code "55") (name "Net-(IC2A-IREF)") (class "Default")
      (node (ref "IC2") (pin "31") (pinfunction "IREF_31") (pintype "bidirectional"))
      (node (ref "R51") (pin "1") (pinfunction "1_1") (pintype "passive"))
    )
    (net (code "56") (name "Net-(LED1-PadC)") (class "Default")
      (node (ref "LED1") (pin "C") (pinfunction "C_C") (pintype "passive"))
      (node (ref "R4") (pin "2") (pinfunction "2_2") (pintype "passive"))
    )
    (net (code "57") (name "Net-(LED2-PadC)") (class "Default")
      (node (ref "LED2") (pin "C") (pinfunction "C_C") (pintype "passive"))
      (node (ref "R5") (pin "2") (pinfunction "2_2") (pintype "passive"))
    )
    (net (code "58") (name "Net-(LED3-PadC)") (class "Default")
      (node (ref "LED3") (pin "C") (pinfunction "C_C") (pintype "passive"))
      (node (ref "R6") (pin "2") (pinfunction "2_2") (pintype "passive"))
    )
    (net (code "59") (name "Net-(LED4-PadC)") (class "Default")
      (node (ref "LED4") (pin "C") (pinfunction "C_C") (pintype "passive"))
      (node (ref "R10") (pin "2") (pinfunction "2_2") (pintype "passive"))
    )
    (net (code "60") (name "Net-(LED5-PadC)") (class "Default")
      (node (ref "LED5") (pin "C") (pinfunction "C_C") (pintype "passive"))
      (node (ref "R11") (pin "2") (pinfunction "2_2") (pintype "passive"))
    )
    (net (code "61") (name "Net-(LED6-PadC)") (class "Default")
      (node (ref "LED6") (pin "C") (pinfunction "C_C") (pintype "passive"))
      (node (ref "R12") (pin "2") (pinfunction "2_2") (pintype "passive"))
    )
    (net (code "62") (name "Net-(LED7-PadC)") (class "Default")
      (node (ref "LED7") (pin "C") (pinfunction "C_C") (pintype "passive"))
      (node (ref "R16") (pin "2") (pinfunction "2_2") (pintype "passive"))
    )
    (net (code "63") (name "Net-(LED8-PadC)") (class "Default")
      (node (ref "LED8") (pin "C") (pinfunction "C_C") (pintype "passive"))
      (node (ref "R17") (pin "2") (pinfunction "2_2") (pintype "passive"))
    )
    (net (code "64") (name "Net-(LED9-PadC)") (class "Default")
      (node (ref "LED9") (pin "C") (pinfunction "C_C") (pintype "passive"))
      (node (ref "R18") (pin "2") (pinfunction "2_2") (pintype "passive"))
    )
    (net (code "65") (name "Net-(LED10-PadC)") (class "Default")
      (node (ref "LED10") (pin "C") (pinfunction "C_C") (pintype "passive"))
      (node (ref "R22") (pin "2") (pinfunction "2_2") (pintype "passive"))
    )
    (net (code "66") (name "Net-(LED11-PadC)") (class "Default")
      (node (ref "LED11") (pin "C") (pinfunction "C_C") (pintype "passive"))
      (node (ref "R23") (pin "2") (pinfunction "2_2") (pintype "passive"))
    )
    (net (code "67") (name "Net-(LED12-PadC)") (class "Default")
      (node (ref "LED12") (pin "C") (pinfunction "C_C") (pintype "passive"))
      (node (ref "R24") (pin "2") (pinfunction "2_2") (pintype "passive"))
    )
    (net (code "68") (name "Net-(LED13-PadC)") (class "Default")
      (node (ref "LED13") (pin "C") (pinfunction "C_C") (pintype "passive"))
      (node (ref "R28") (pin "2") (pinfunction "2_2") (pintype "passive"))
    )
    (net (code "69") (name "Net-(LED14-PadC)") (class "Default")
      (node (ref "LED14") (pin "C") (pinfunction "C_C") (pintype "passive"))
      (node (ref "R29") (pin "2") (pinfunction "2_2") (pintype "passive"))
    )
    (net (code "70") (name "Net-(LED15-PadC)") (class "Default")
      (node (ref "LED15") (pin "C") (pinfunction "C_C") (pintype "passive"))
      (node (ref "R30") (pin "2") (pinfunction "2_2") (pintype "passive"))
    )
    (net (code "71") (name "Net-(LED16-PadC)") (class "Default")
      (node (ref "LED16") (pin "C") (pinfunction "C_C") (pintype "passive"))
      (node (ref "R34") (pin "2") (pinfunction "2_2") (pintype "passive"))
    )
    (net (code "72") (name "Net-(LED17-PadC)") (class "Default")
      (node (ref "LED17") (pin "C") (pinfunction "C_C") (pintype "passive"))
      (node (ref "R35") (pin "2") (pinfunction "2_2") (pintype "passive"))
    )
    (net (code "73") (name "Net-(LED18-PadC)") (class "Default")
      (node (ref "LED18") (pin "C") (pinfunction "C_C") (pintype "passive"))
      (node (ref "R36") (pin "2") (pinfunction "2_2") (pintype "passive"))
    )
    (net (code "74") (name "Net-(LED19-PadC)") (class "Default")
      (node (ref "LED19") (pin "C") (pinfunction "C_C") (pintype "passive"))
      (node (ref "R40") (pin "2") (pinfunction "2_2") (pintype "passive"))
    )
    (net (code "75") (name "Net-(LED20-PadC)") (class "Default")
      (node (ref "LED20") (pin "C") (pinfunction "C_C") (pintype "passive"))
      (node (ref "R41") (pin "2") (pinfunction "2_2") (pintype "passive"))
    )
    (net (code "76") (name "Net-(LED21-PadC)") (class "Default")
      (node (ref "LED21") (pin "C") (pinfunction "C_C") (pintype "passive"))
      (node (ref "R42") (pin "2") (pinfunction "2_2") (pintype "passive"))
    )
    (net (code "77") (name "Net-(LED22-PadC)") (class "Default")
      (node (ref "LED22") (pin "C") (pinfunction "C_C") (pintype "passive"))
      (node (ref "R46") (pin "2") (pinfunction "2_2") (pintype "passive"))
    )
    (net (code "78") (name "Net-(LED23-PadC)") (class "Default")
      (node (ref "LED23") (pin "C") (pinfunction "C_C") (pintype "passive"))
      (node (ref "R47") (pin "2") (pinfunction "2_2") (pintype "passive"))
    )
    (net (code "79") (name "Net-(LED24-PadC)") (class "Default")
      (node (ref "LED24") (pin "C") (pinfunction "C_C") (pintype "passive"))
      (node (ref "R48") (pin "2") (pinfunction "2_2") (pintype "passive"))
    )
    (net (code "80") (name "Net-(LED25-PadC)") (class "Default")
      (node (ref "LED25") (pin "C") (pinfunction "C_C") (pintype "passive"))
      (node (ref "R50") (pin "2") (pinfunction "2_2") (pintype "passive"))
    )
    (net (code "81") (name "unconnected-(IC2A-SOUT-Pad29)") (class "Default")
      (node (ref "IC2") (pin "29") (pinfunction "SOUT_29") (pintype "output"))
    )
  )
)
